# PX4uNode_V0_1_3.net
KiCad netlist of a schematic drawn in EAGLE
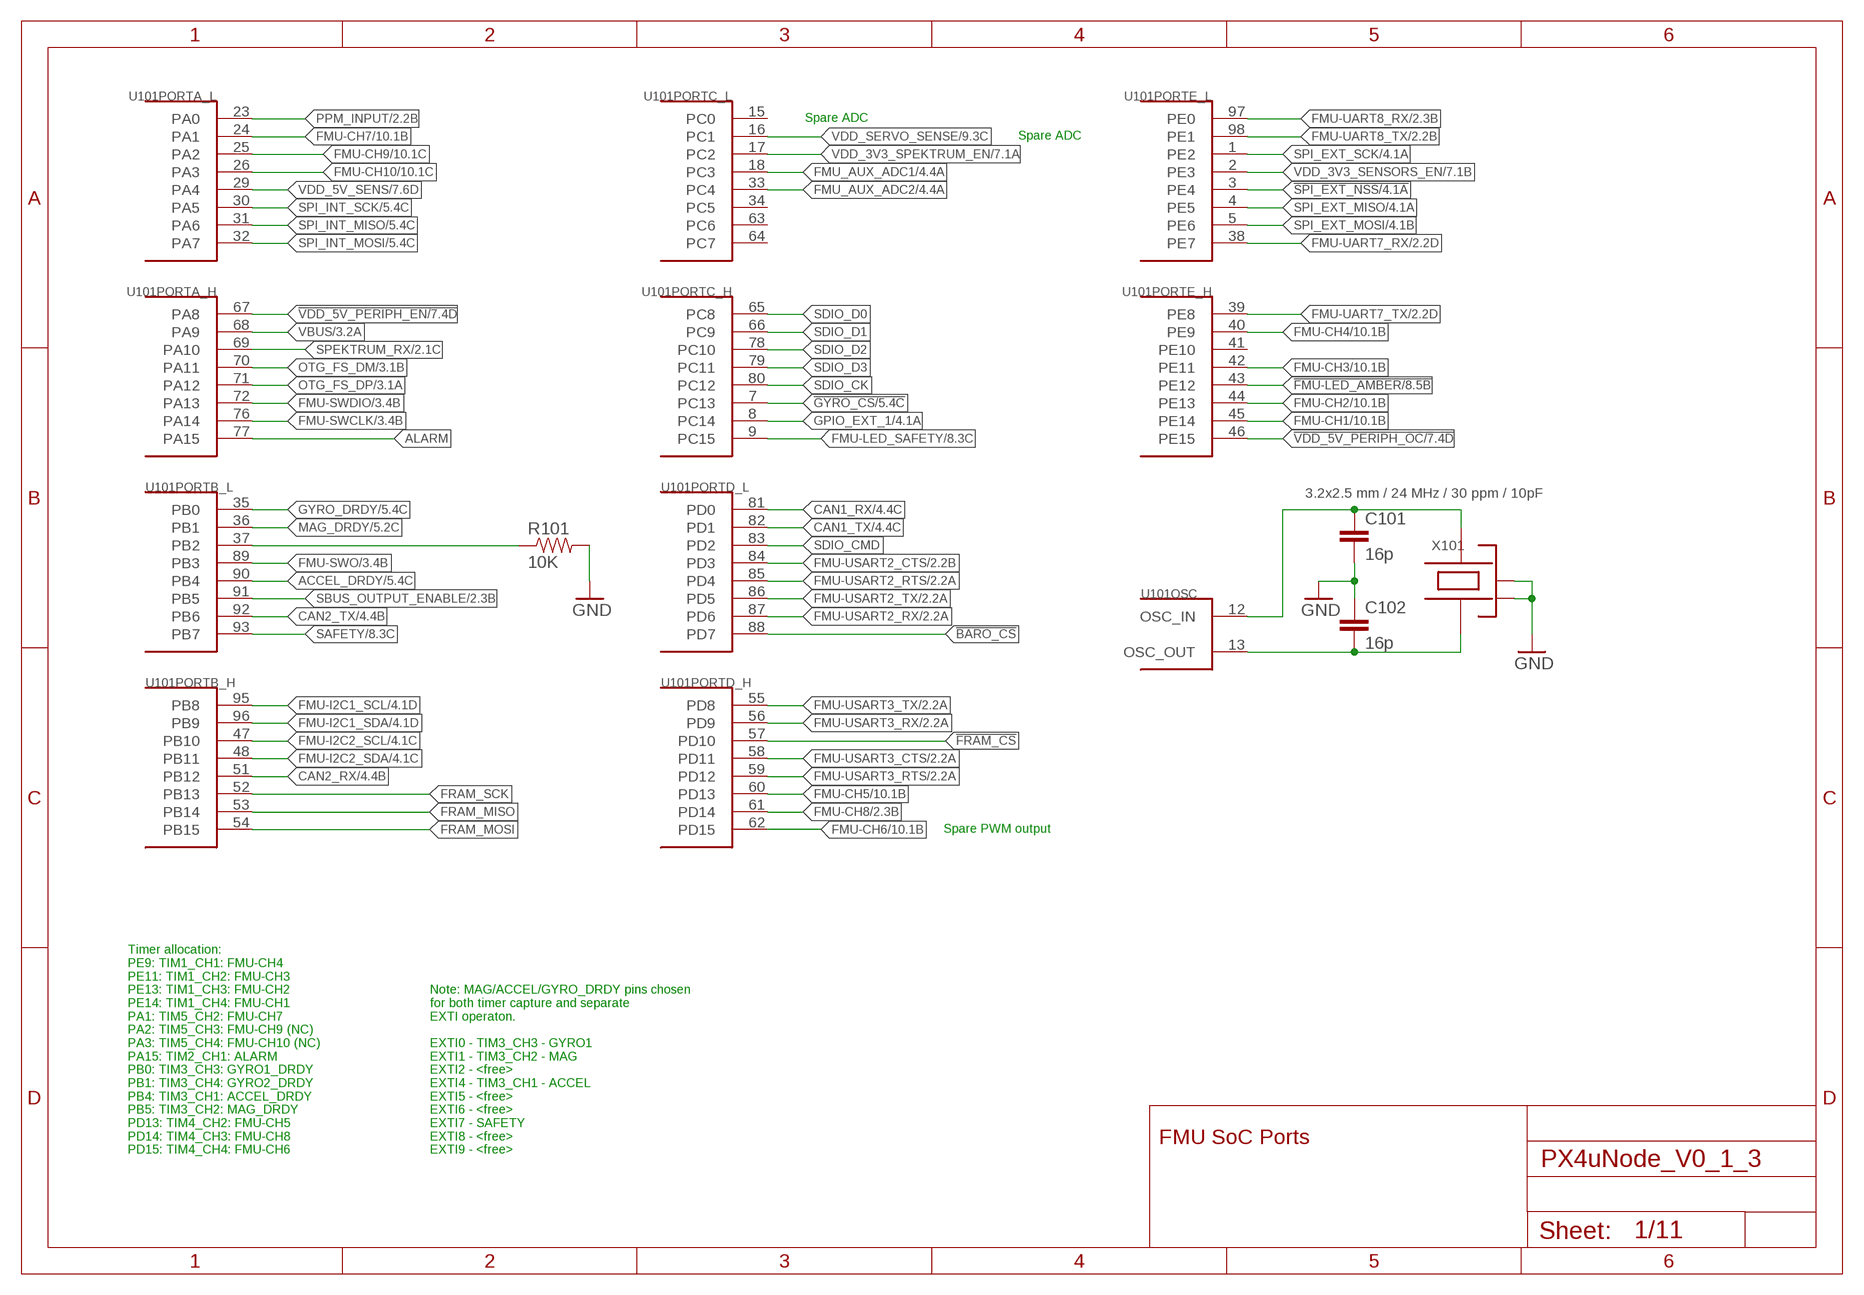
[diagram p0: schematic, sheet 1]
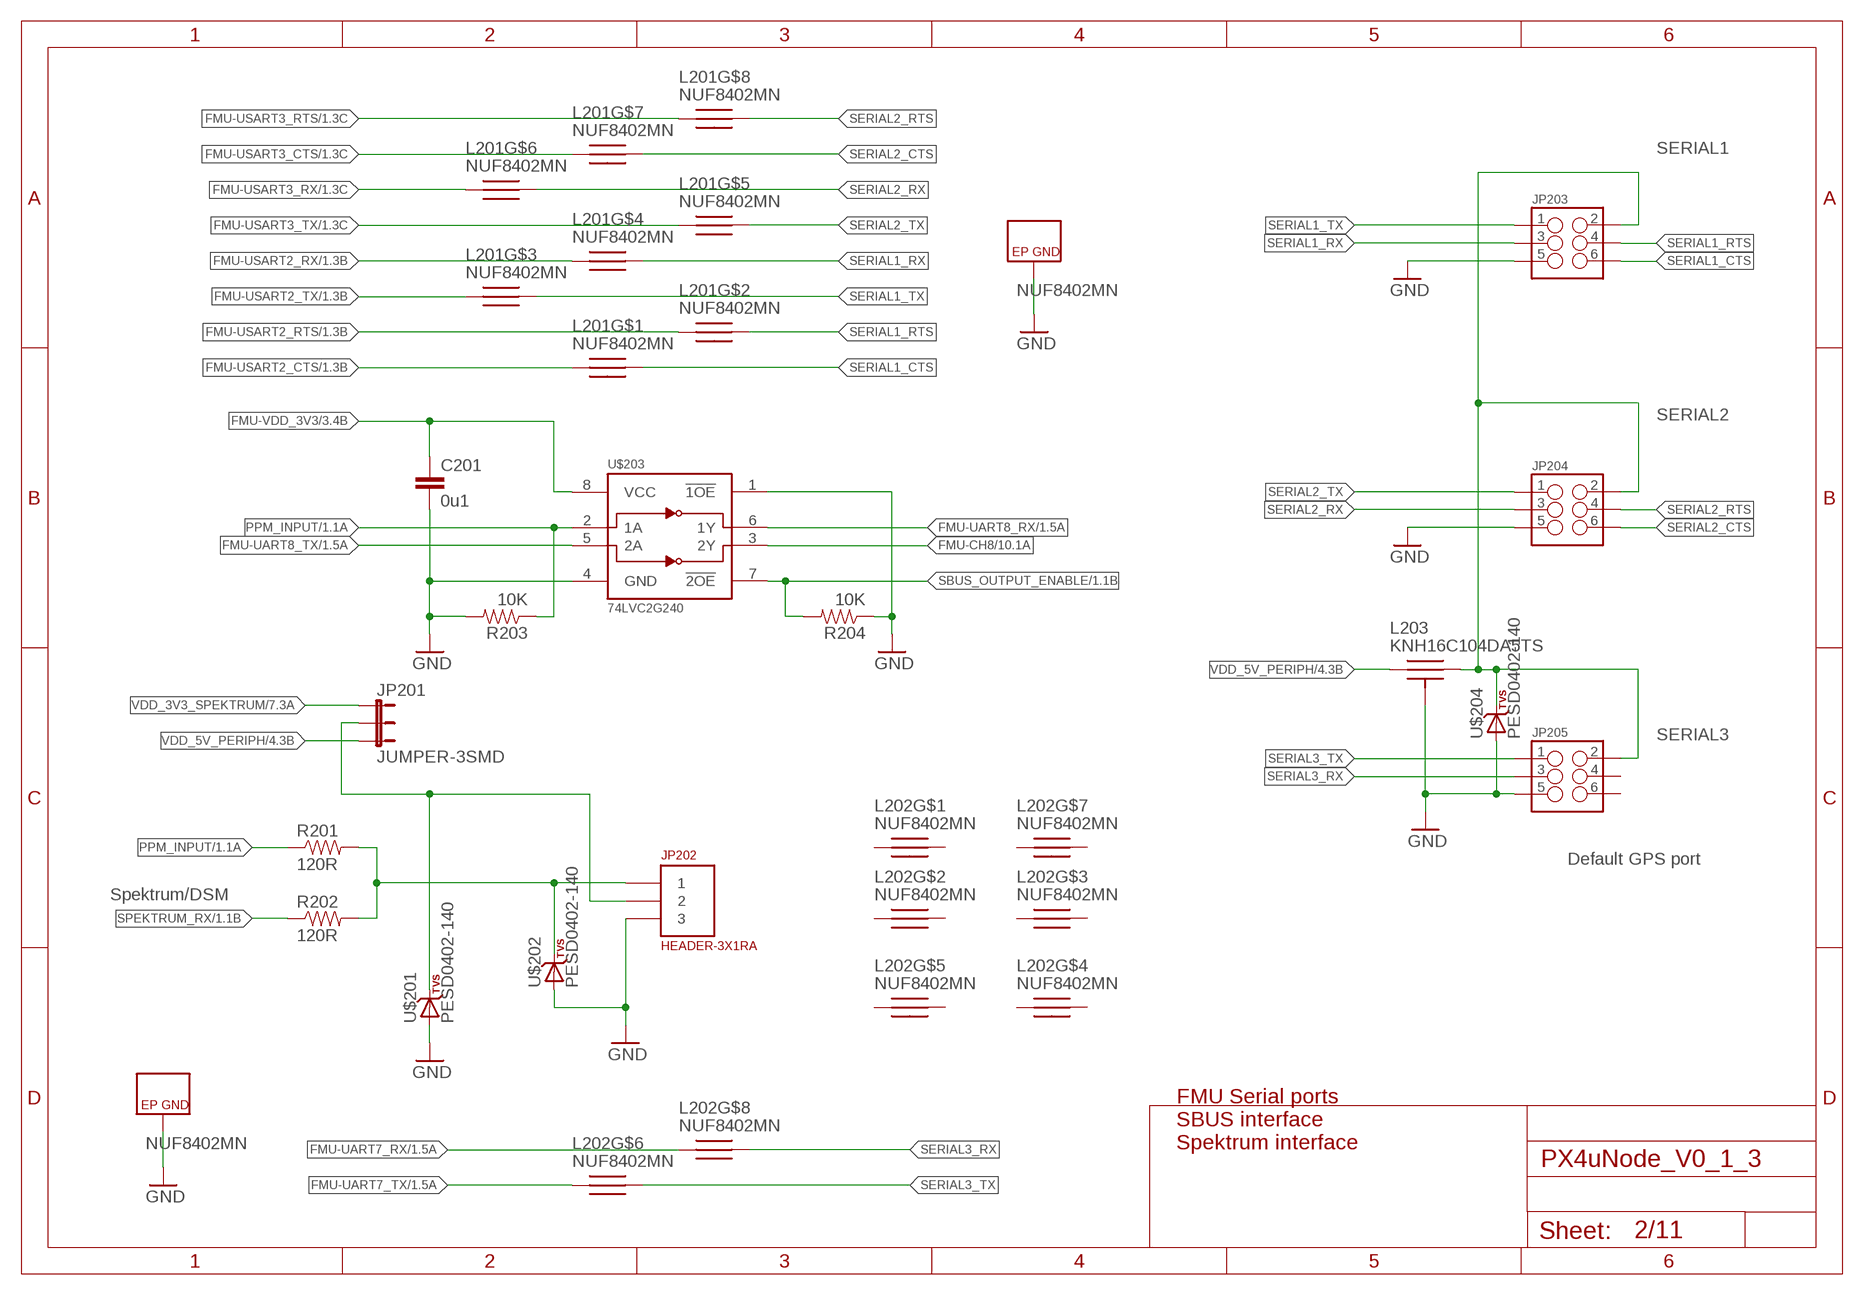
[diagram p1: schematic, sheet 2]
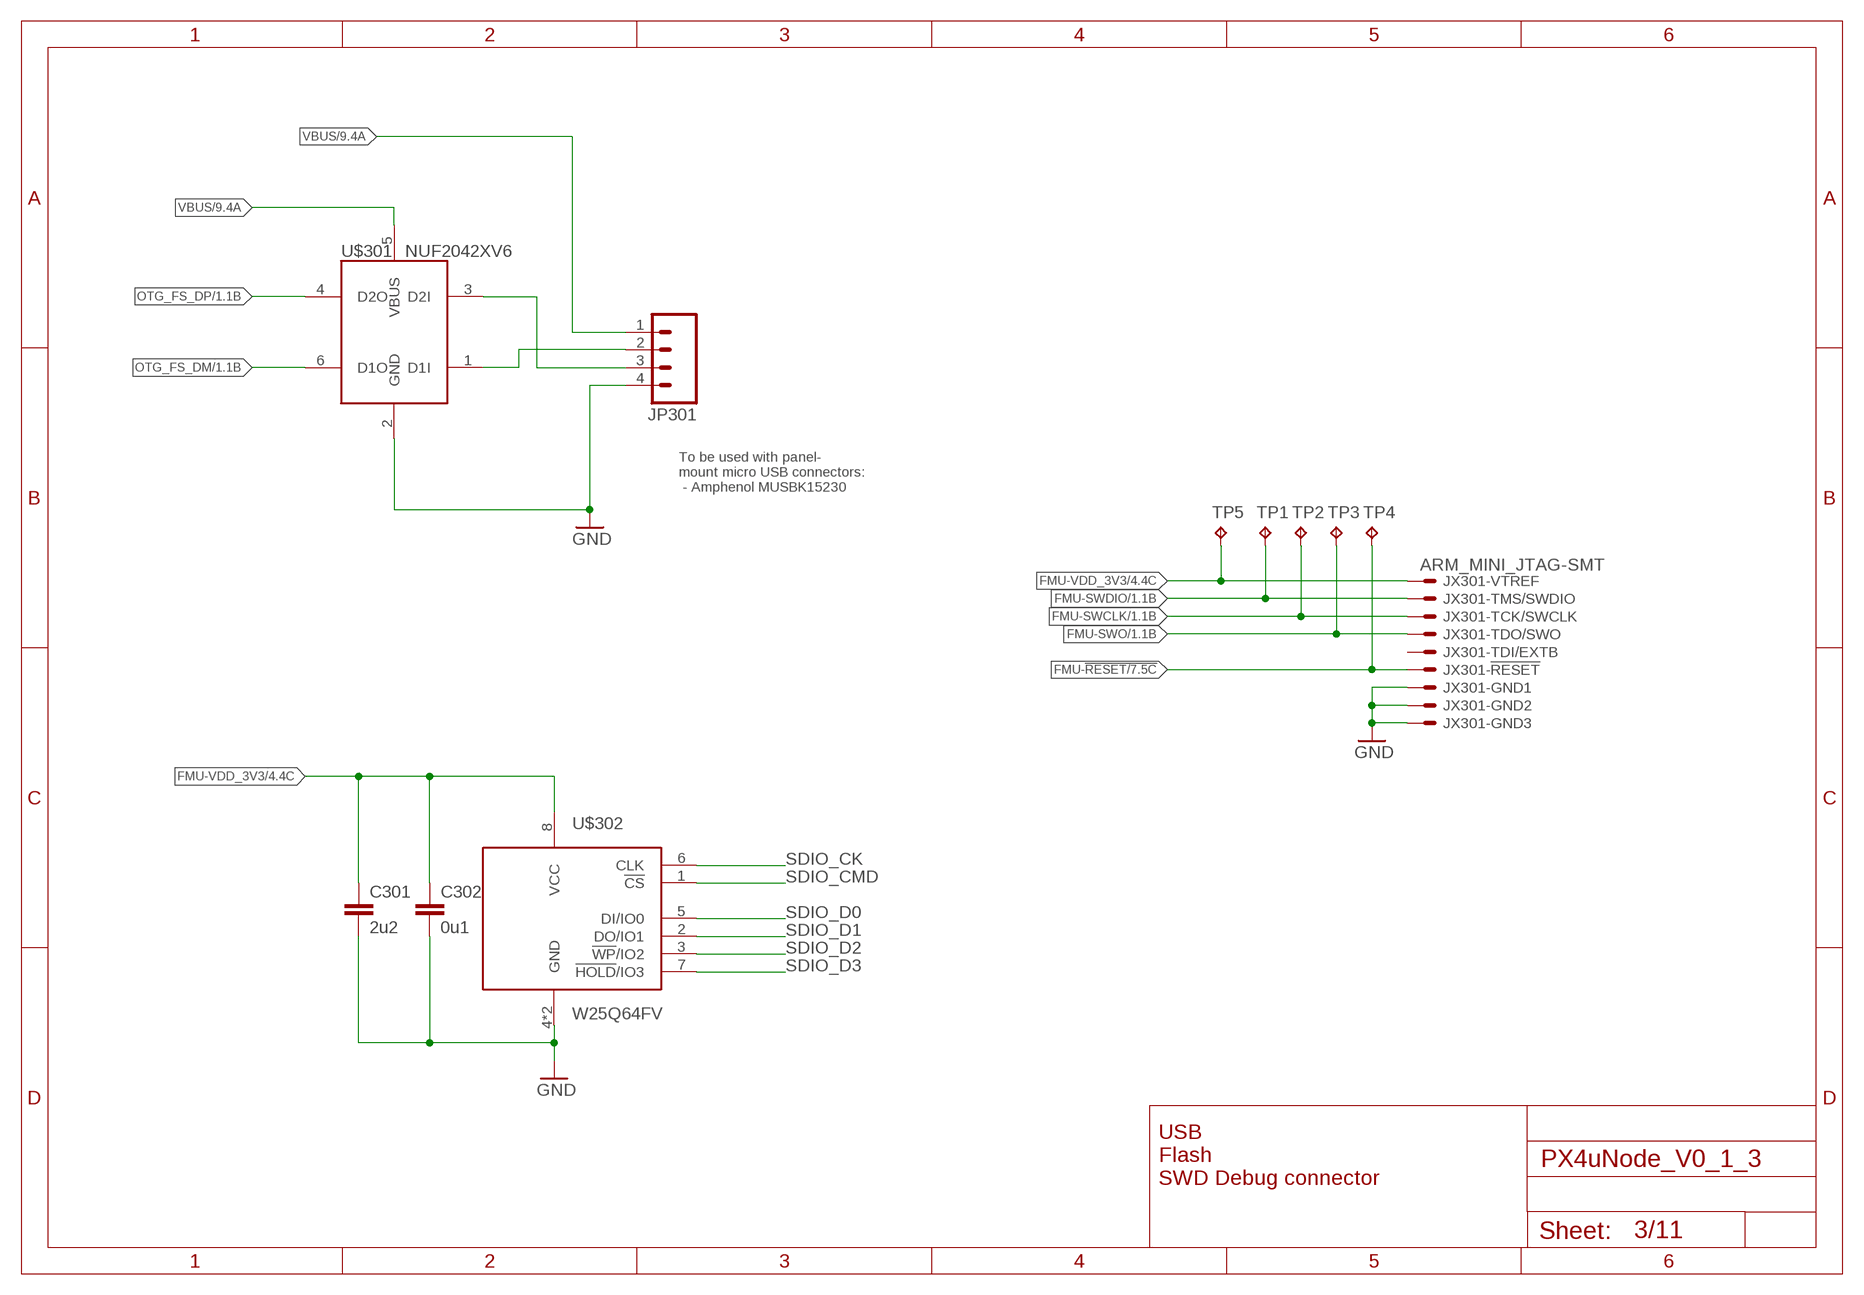
[diagram p2: schematic, sheet 3]
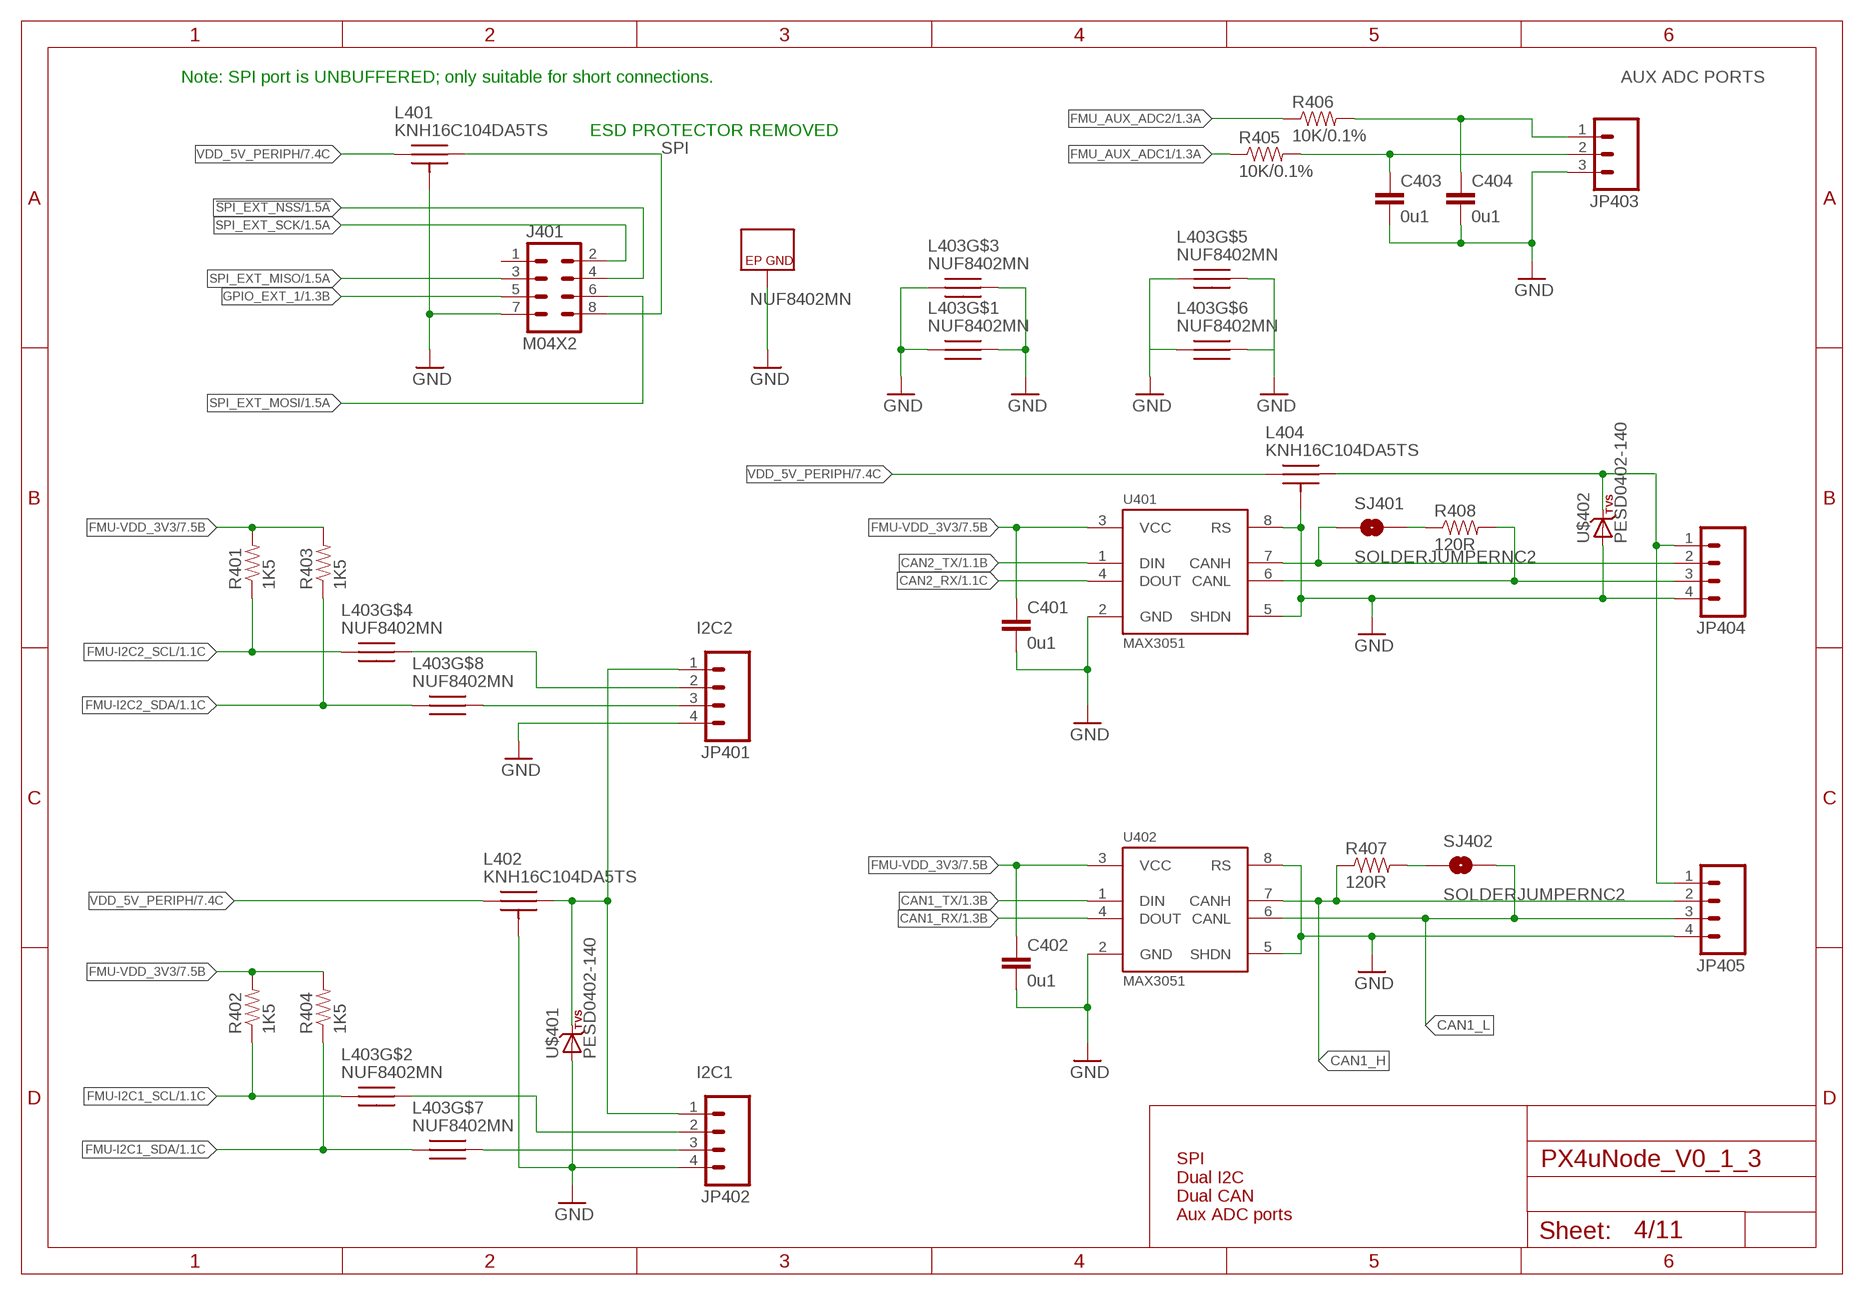
[diagram p3: schematic, sheet 4]
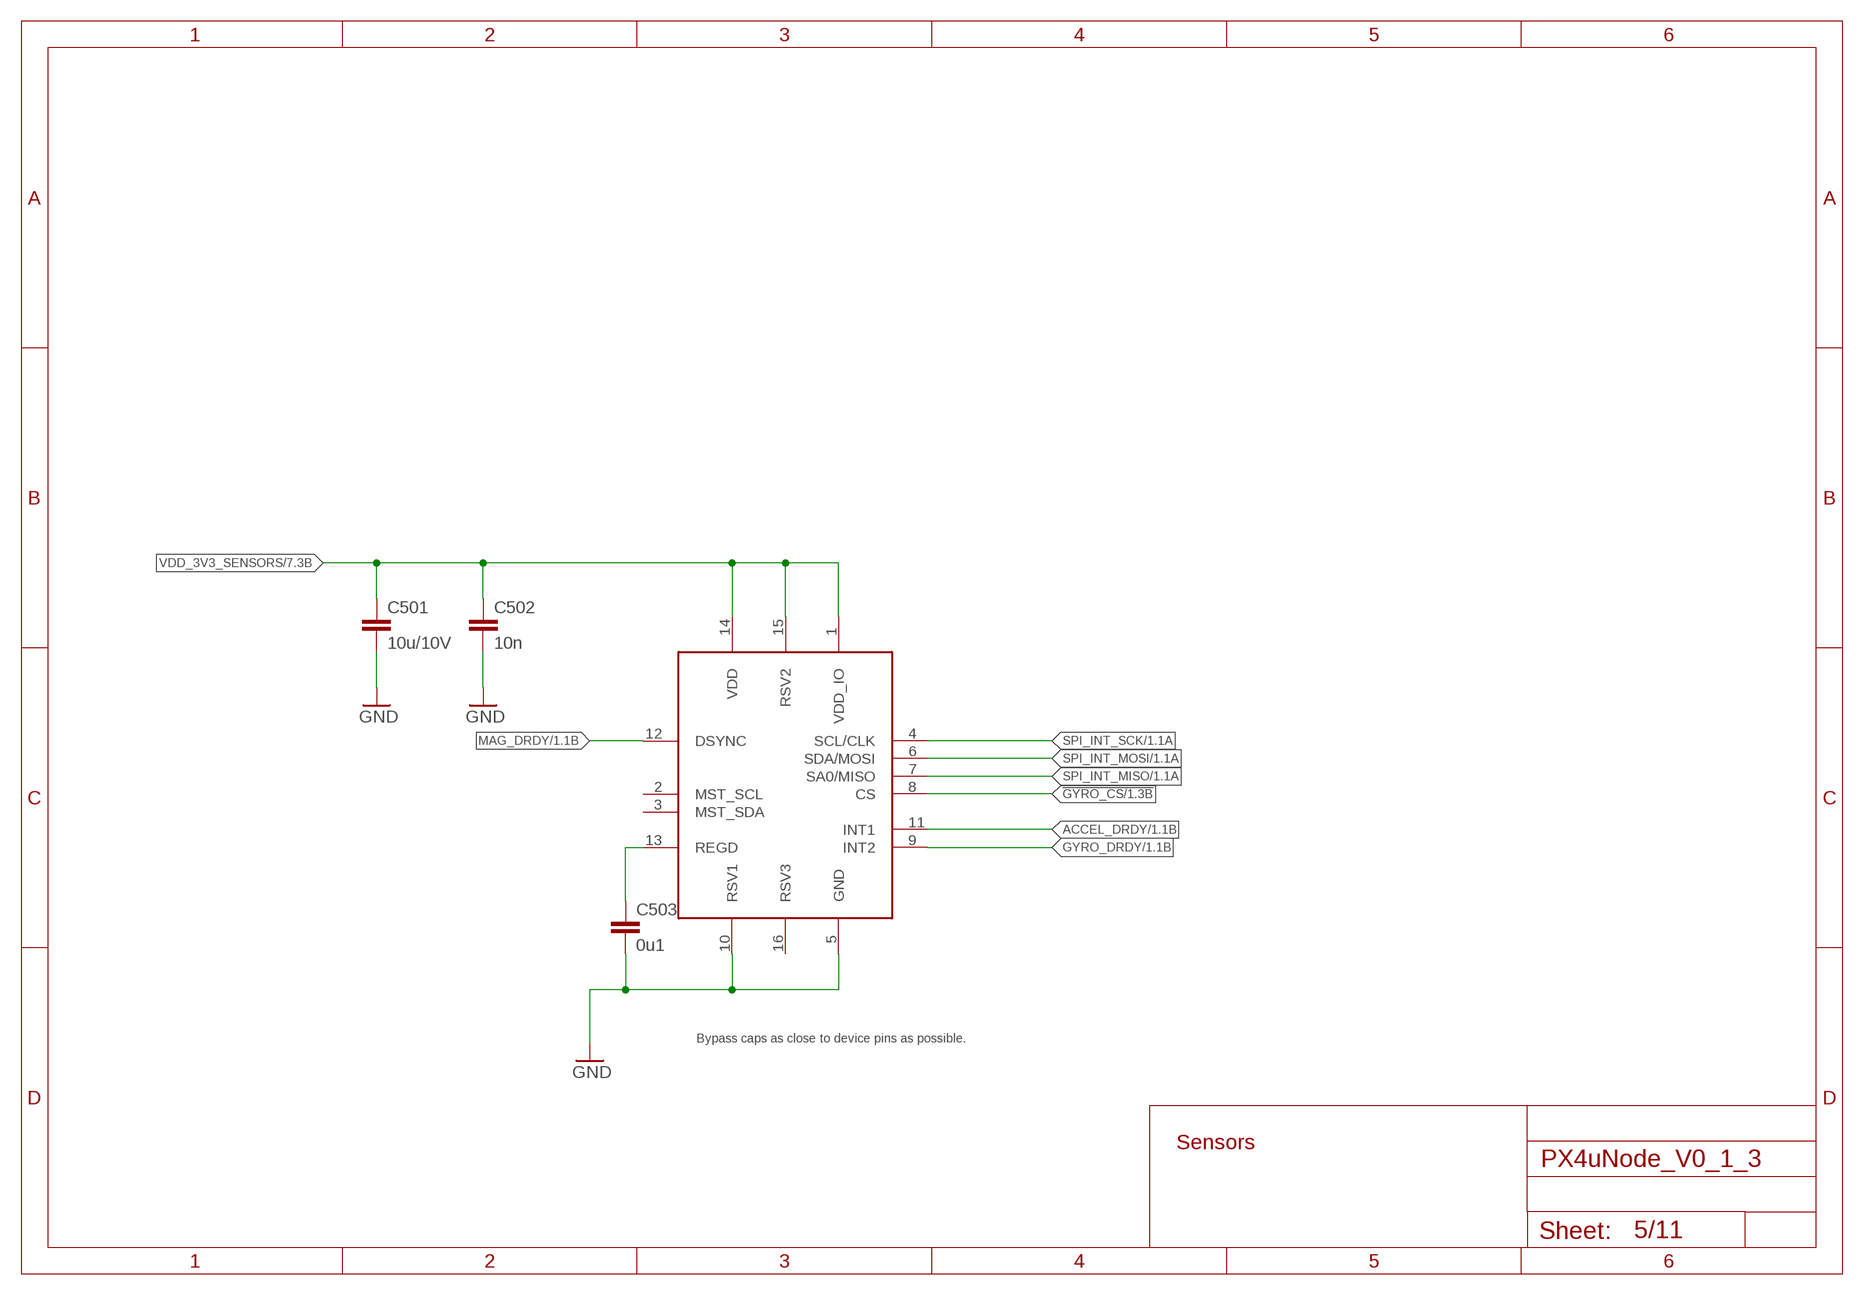
[diagram p4: schematic, sheet 5]
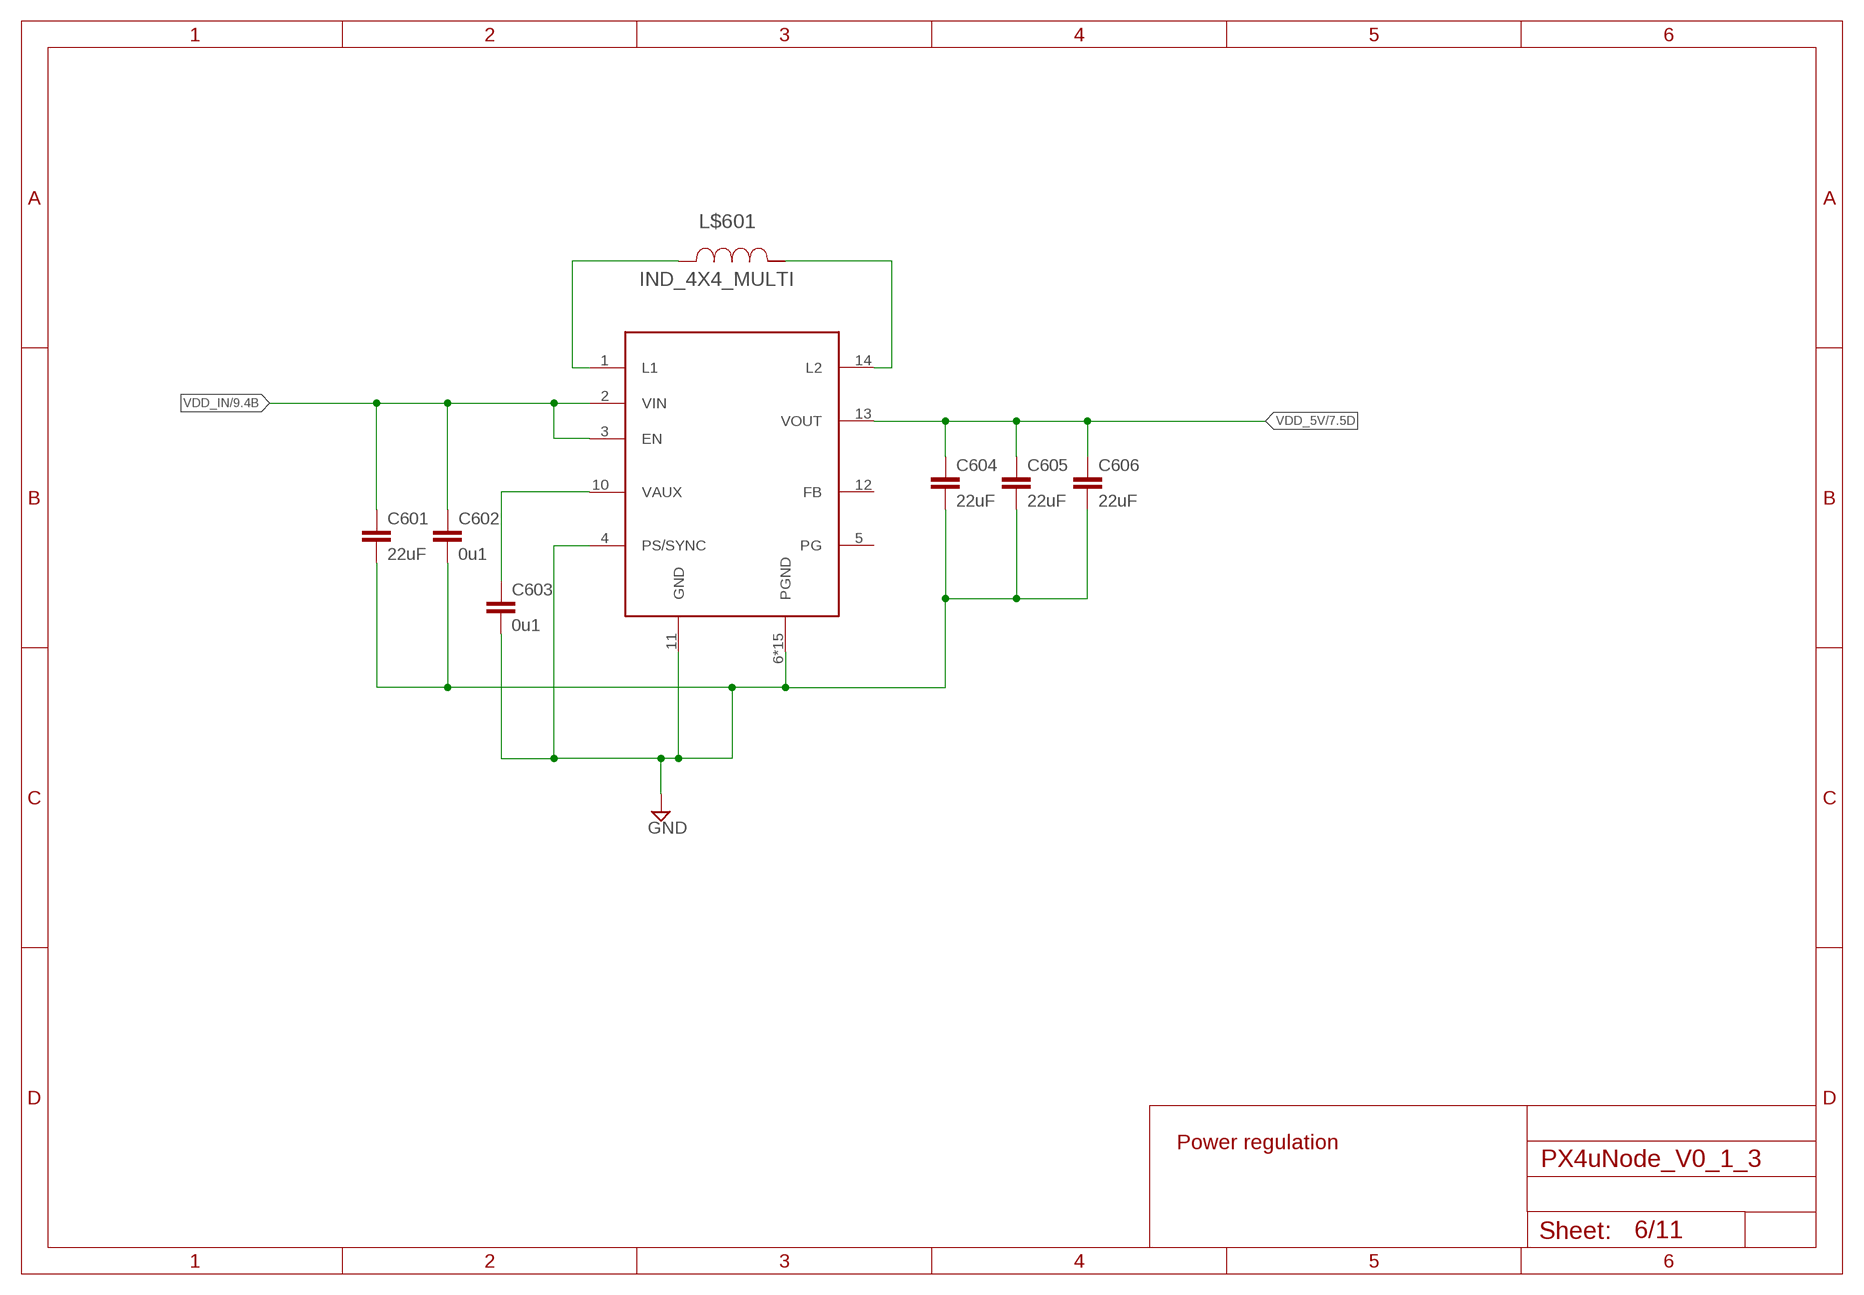
[diagram p5: schematic, sheet 6]
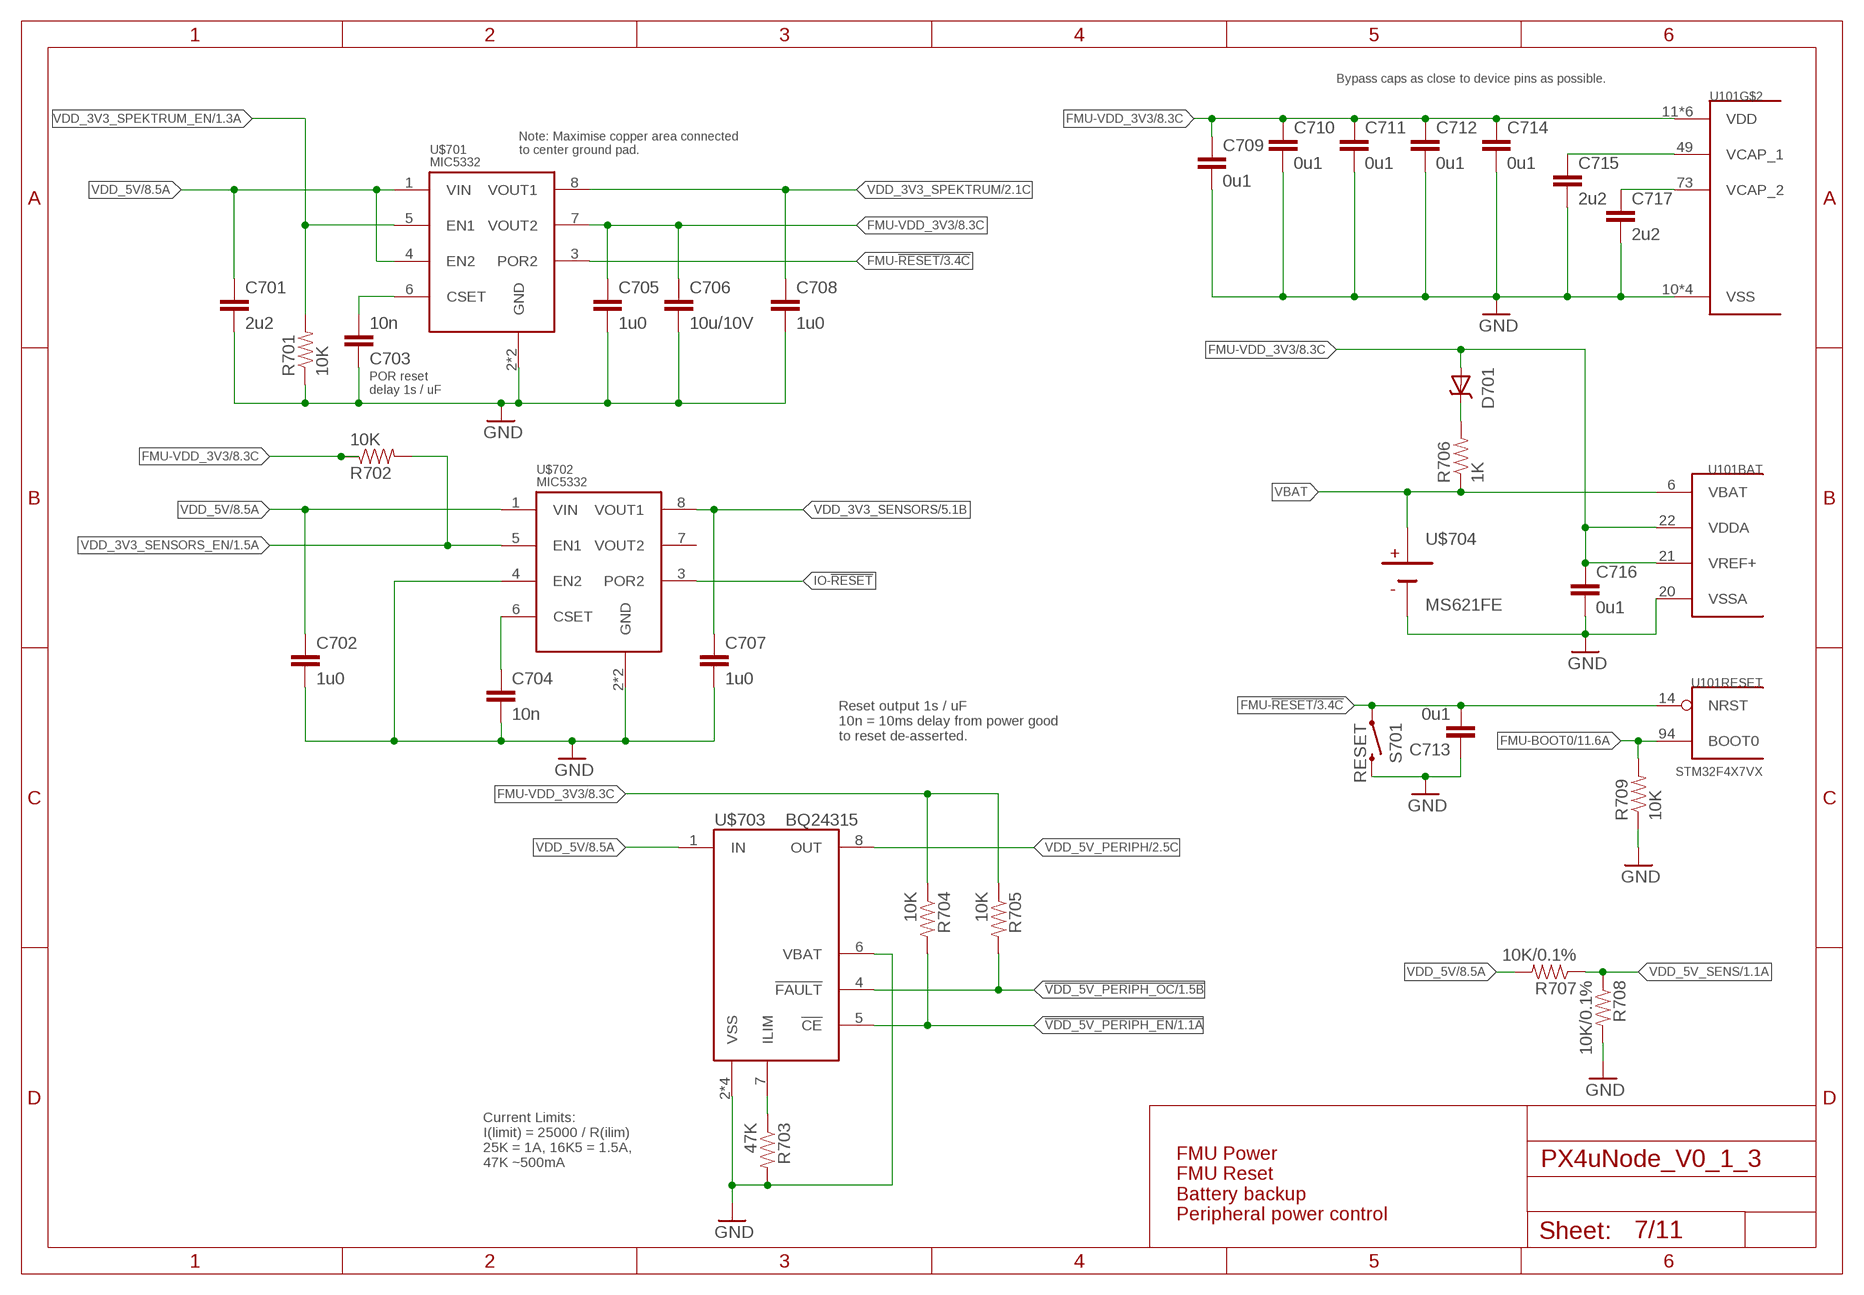
[diagram p6: schematic, sheet 7]
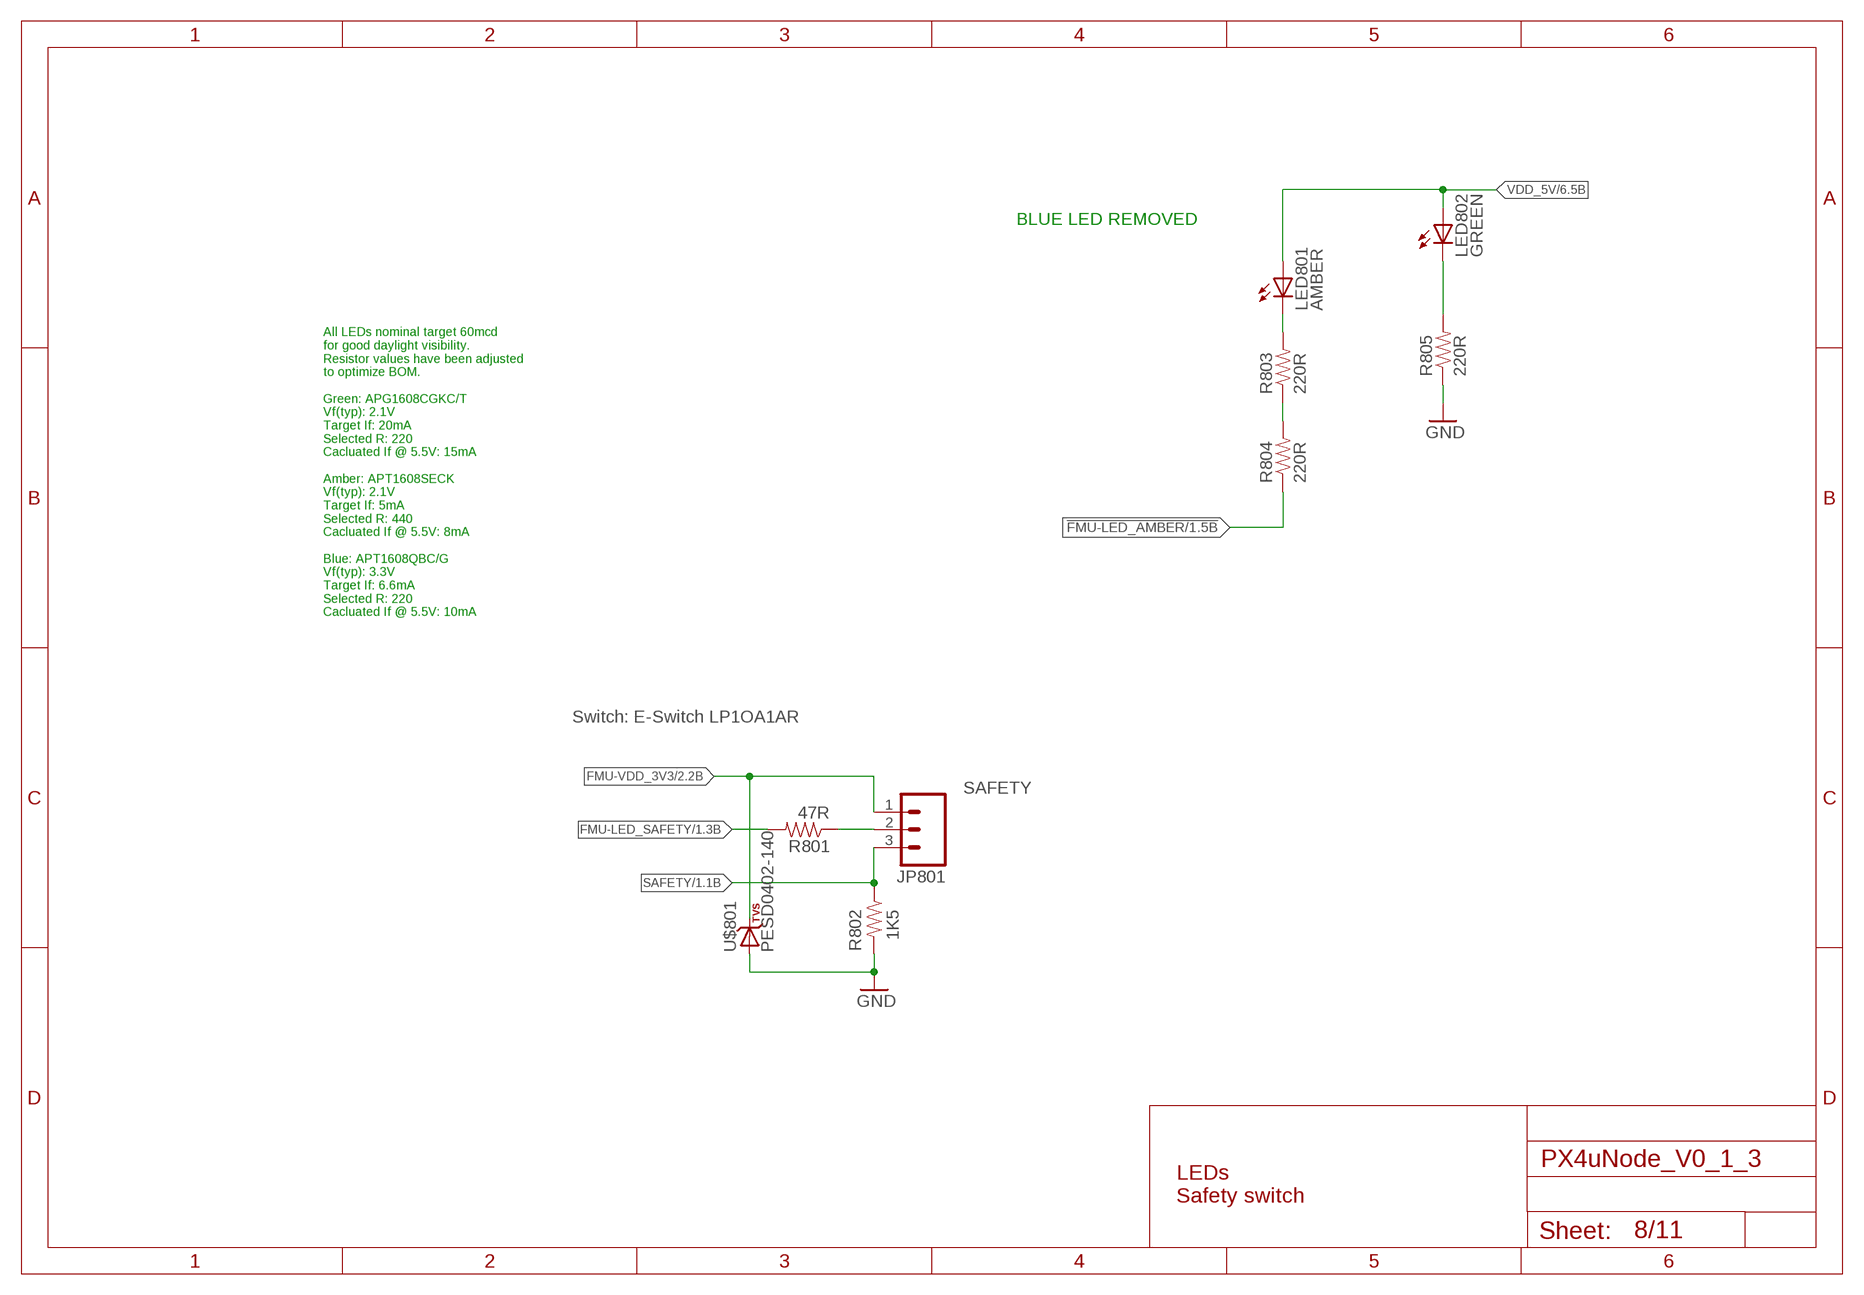
[diagram p7: schematic, sheet 8]
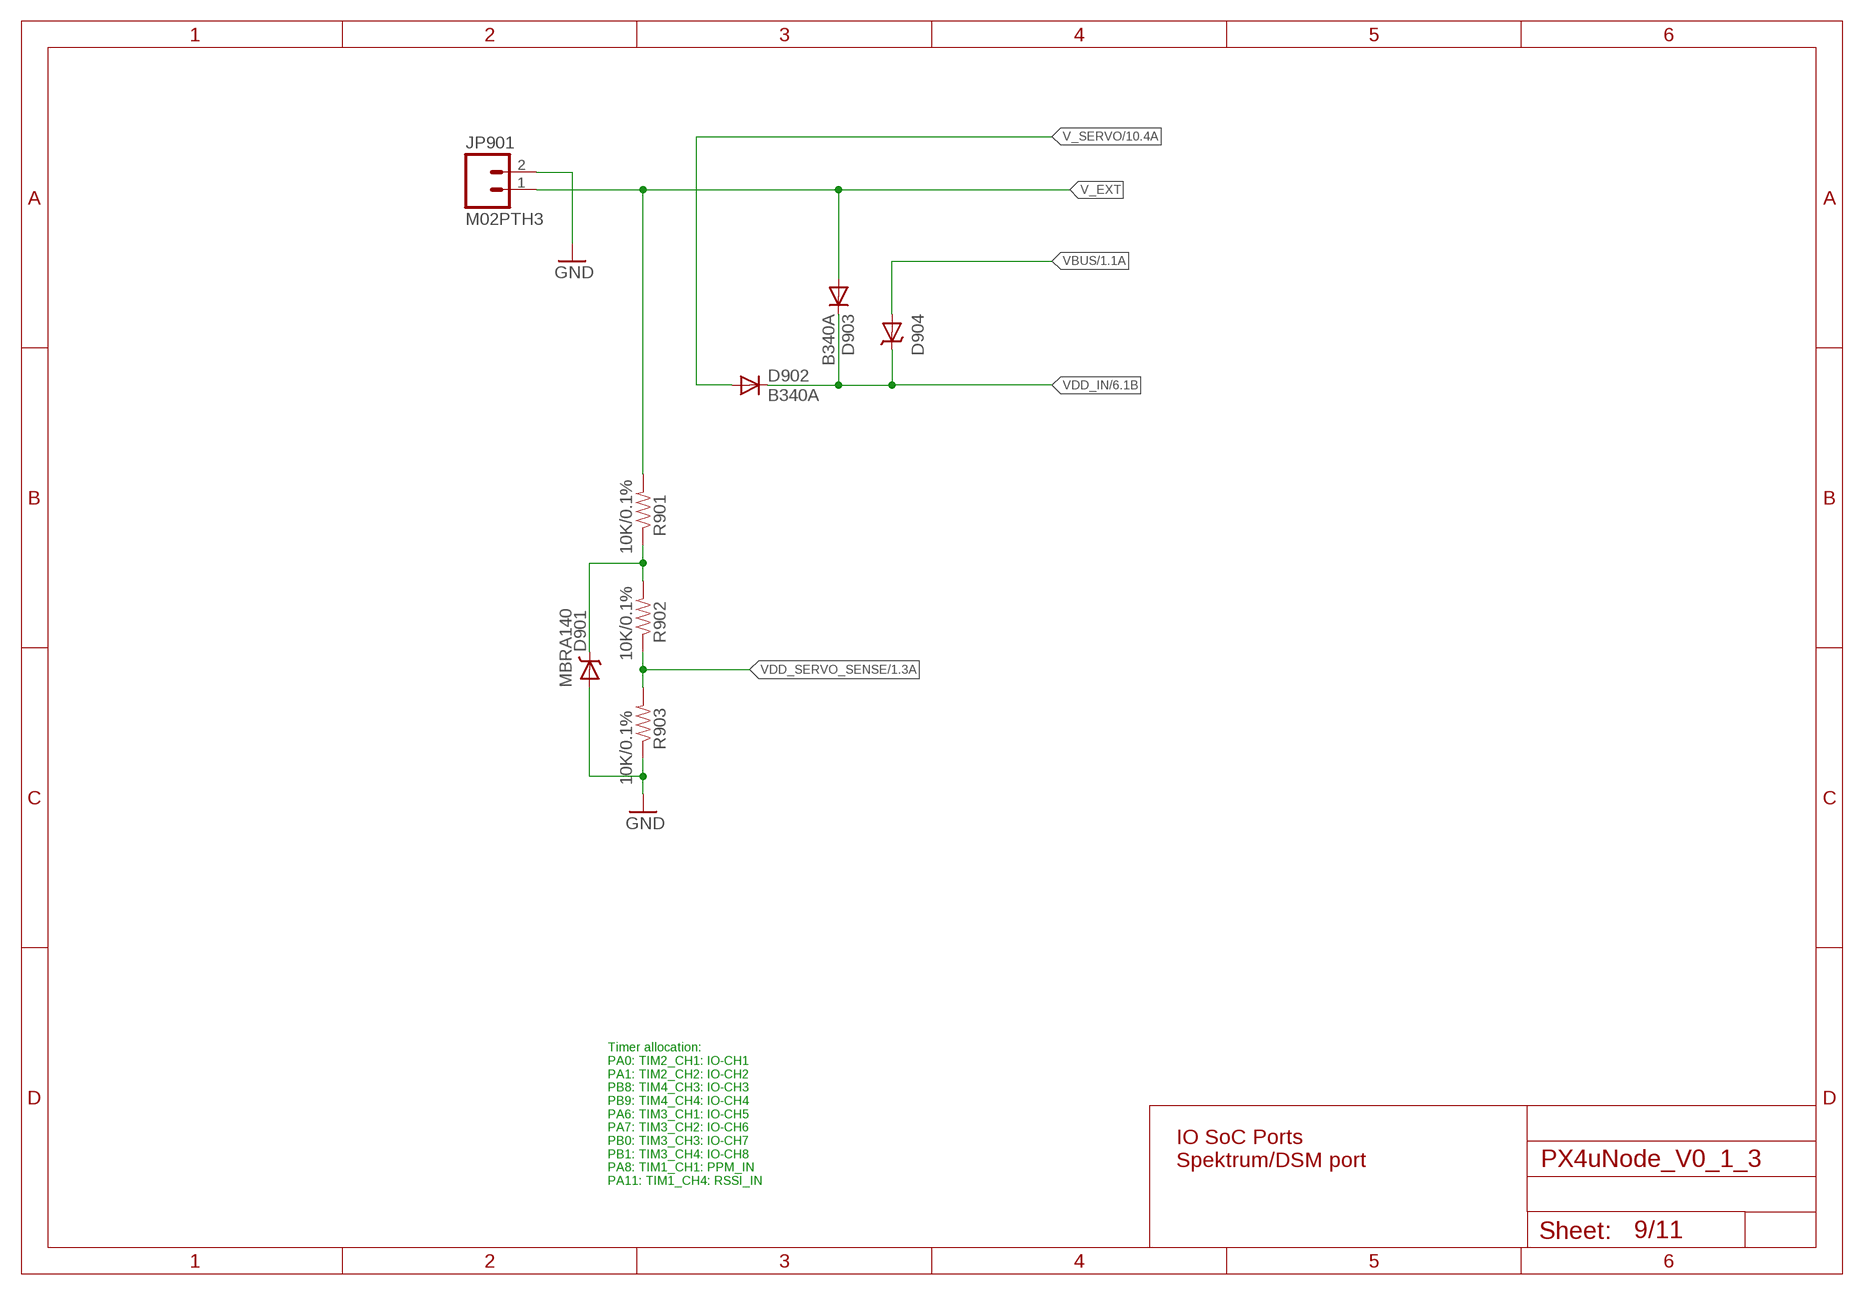
[diagram p8: schematic, sheet 9]
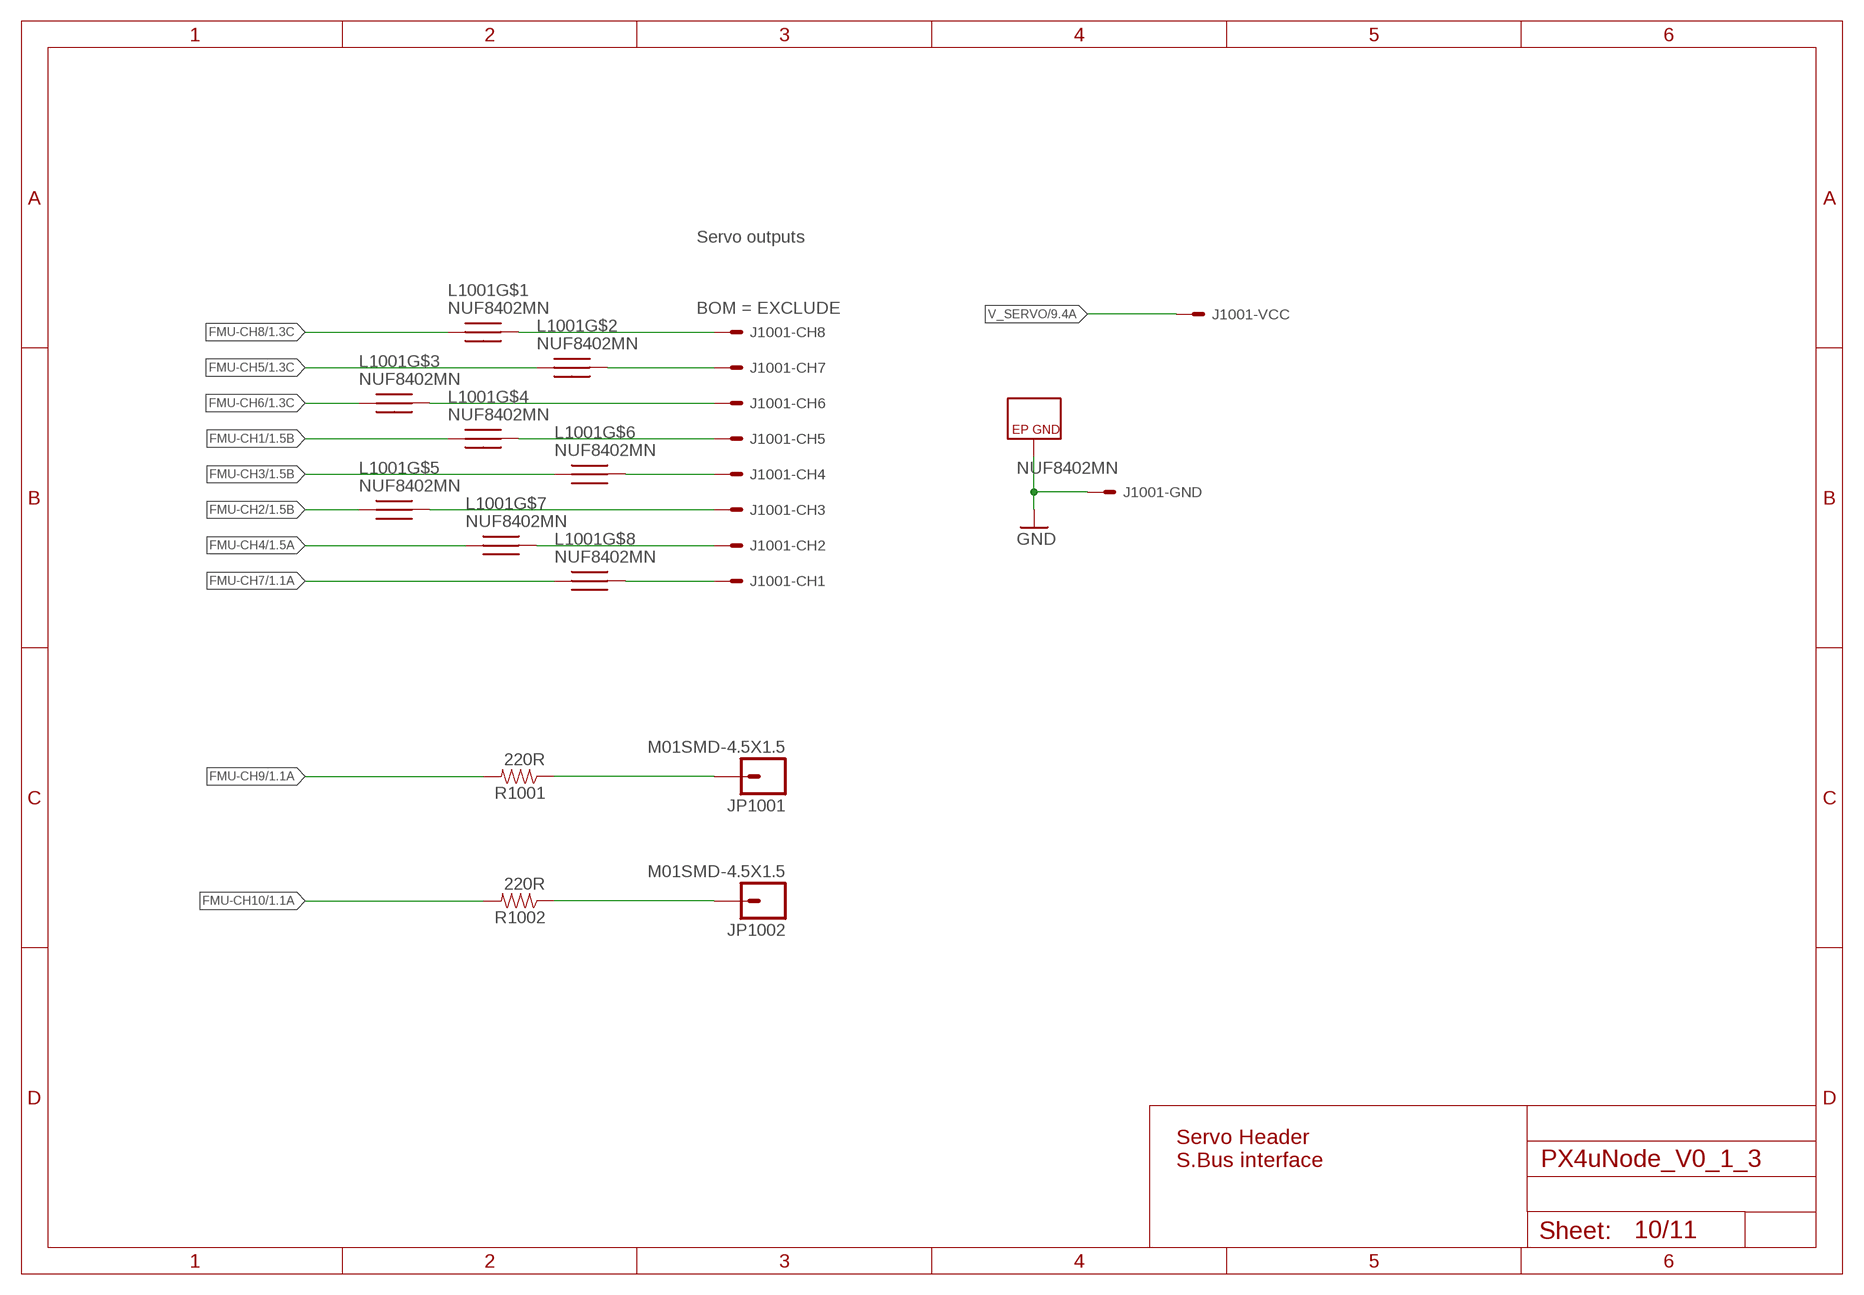
[diagram p9: schematic, sheet 10]
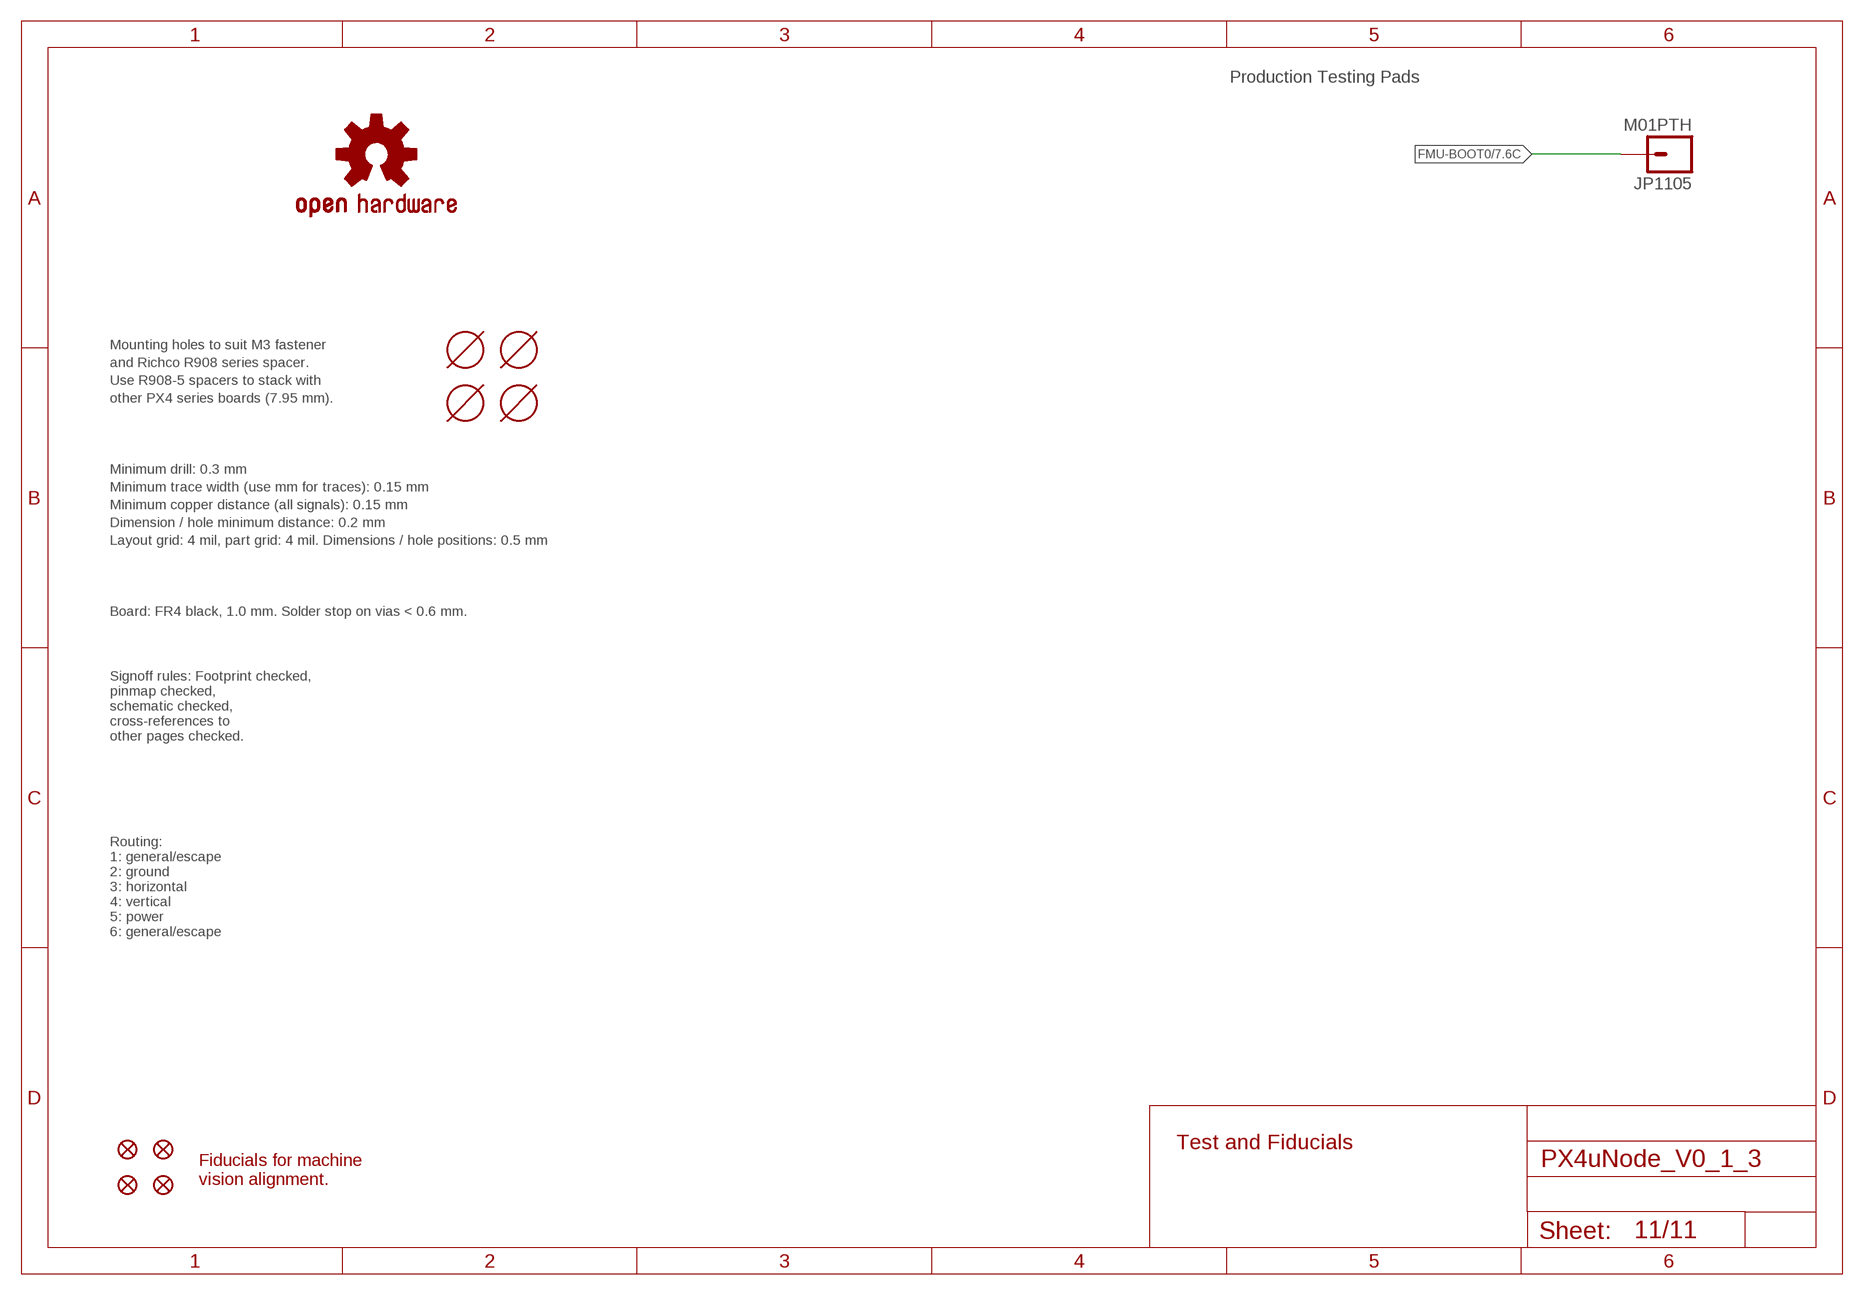
[diagram p10: schematic, sheet 11]

(export (version "E")
  (design (tool "Eeschema 10.0.6"))
  (components
    (comp (ref "C601")
      (value "22uF")
      (footprint "eagle-import:1210")
      (fields (field (name "PARTNO") "C3225X7R1C226M250AC"))
      (libsource (lib "eagle-import") (part "22UF-16V-20%-(1210)"))
    )
    (comp (ref "C602")
      (value "0u1")
      (footprint "eagle-import:0402-CAP")
      (fields (field (name "PARTNO") "CC0402ZRY5V7BB104"))
      (libsource (lib "eagle-import") (part "CAP0402"))
    )
    (comp (ref "C603")
      (value "0u1")
      (footprint "eagle-import:0402-CAP")
      (fields (field (name "PARTNO") "CC0402ZRY5V7BB104"))
      (libsource (lib "eagle-import") (part "CAP0402"))
    )
    (comp (ref "C604")
      (value "22uF")
      (footprint "eagle-import:1210")
      (fields (field (name "PARTNO") "C3225X7R1C226M250AC"))
      (libsource (lib "eagle-import") (part "22UF-16V-20%-(1210)"))
    )
    (comp (ref "C605")
      (value "22uF")
      (footprint "eagle-import:1210")
      (fields (field (name "PARTNO") "C3225X7R1C226M250AC"))
      (libsource (lib "eagle-import") (part "22UF-16V-20%-(1210)"))
    )
    (comp (ref "C606")
      (value "22uF")
      (footprint "eagle-import:1210")
      (fields (field (name "PARTNO") "C3225X7R1C226M250AC"))
      (libsource (lib "eagle-import") (part "22UF-16V-20%-(1210)"))
    )
    (comp (ref "L$601")
      (value "IND_4X4_MULTI")
      (footprint "eagle-import:IND_4X4_MULTI")
      (fields (field (name "MANUFACTURER_PART_NUMBER") "XFL4020-222MEB"))
      (libsource (lib "eagle-import") (part "IND_4X4_MULTI"))
    )
    (comp (ref "U$601")
      (value "TPS6303X")
      (footprint "eagle-import:PWSON10")
      (fields (field (name "PARTNO") "TPS63061DSCT"))
      (libsource (lib "eagle-import") (part "TPS6303X"))
    )
    (comp (ref "C201")
      (value "0u1")
      (footprint "eagle-import:0402-CAP")
      (fields (field (name "PARTNO") "CC0402ZRY5V7BB104"))
      (libsource (lib "eagle-import") (part "CAP0402"))
    )
    (comp (ref "JP201")
      (value "JUMPER-3SMD")
      (footprint "eagle-import:SJ_3")
      (libsource (lib "eagle-import") (part "JUMPER-3SMD"))
    )
    (comp (ref "JP202")
      (value "HEADER-3X1RA")
      (footprint "eagle-import:3X1RA")
      (libsource (lib "eagle-import") (part "HEADER-3X1RA"))
    )
    (comp (ref "JP203")
      (value "M03X22X3_SILK_SM")
      (footprint "eagle-import:2X3")
      (libsource (lib "eagle-import") (part "M03X22X3_SILK_SM"))
    )
    (comp (ref "JP204")
      (value "M03X22X3_SILK_SM")
      (footprint "eagle-import:2X3")
      (libsource (lib "eagle-import") (part "M03X22X3_SILK_SM"))
    )
    (comp (ref "JP205")
      (value "M03X22X3_SILK_SM")
      (footprint "eagle-import:2X3")
      (libsource (lib "eagle-import") (part "M03X22X3_SILK_SM"))
    )
    (comp (ref "L201")
      (value "NUF8402MN")
      (footprint "eagle-import:DFN16-THIN")
      (fields (field (name "PARTNO") "NUF8402MN"))
      (libsource (lib "eagle-import") (part "NUF8402MN"))
    )
    (comp (ref "L202")
      (value "NUF8402MN")
      (footprint "eagle-import:DFN16-THIN")
      (fields (field (name "PARTNO") "NUF8402MN"))
      (libsource (lib "eagle-import") (part "NUF8402MN"))
    )
    (comp (ref "L203")
      (value "KNH16C104DA5TS")
      (footprint "eagle-import:KYOCERA-KNH16-DA")
      (libsource (lib "eagle-import") (part "KNH16C104DA5TS"))
    )
    (comp (ref "R201")
      (value "120R")
      (footprint "eagle-import:0402-RES")
      (fields (field (name "PARTNO") "RC0402FR-07120RL"))
      (libsource (lib "eagle-import") (part "RESISTOR0402-RES"))
    )
    (comp (ref "R202")
      (value "120R")
      (footprint "eagle-import:0402-RES")
      (fields (field (name "PARTNO") "RC0402FR-07120RL"))
      (libsource (lib "eagle-import") (part "RESISTOR0402-RES"))
    )
    (comp (ref "R203")
      (value "10K")
      (footprint "eagle-import:0402-RES")
      (fields (field (name "PARTNO") "RC0402FR-0710KL"))
      (libsource (lib "eagle-import") (part "RESISTOR0402-RES"))
    )
    (comp (ref "R204")
      (value "10K")
      (footprint "eagle-import:0402-RES")
      (fields (field (name "PARTNO") "RC0402FR-0710KL"))
      (libsource (lib "eagle-import") (part "RESISTOR0402-RES"))
    )
    (comp (ref "U$201")
      (value "PESD0402-140")
      (footprint "eagle-import:0402-TVS")
      (libsource (lib "eagle-import") (part "DIODE-TVS"))
    )
    (comp (ref "U$202")
      (value "PESD0402-140")
      (footprint "eagle-import:0402-TVS")
      (libsource (lib "eagle-import") (part "DIODE-TVS"))
    )
    (comp (ref "U$203")
      (value "74LVC2G240")
      (footprint "eagle-import:VSSOP8")
      (libsource (lib "eagle-import") (part "74LVC2G240"))
    )
    (comp (ref "U$204")
      (value "PESD0402-140")
      (footprint "eagle-import:0402-TVS")
      (libsource (lib "eagle-import") (part "DIODE-TVS"))
    )
    (comp (ref "C701")
      (value "2u2")
      (footprint "eagle-import:0603-CAP")
      (fields (field (name "PARTNO") "C1608Y5V1C225Z"))
      (libsource (lib "eagle-import") (part "CAP0603"))
    )
    (comp (ref "C702")
      (value "1u0")
      (footprint "eagle-import:0603-CAP")
      (fields (field (name "PARTNO") "CC0603ZRY5V7BB105"))
      (libsource (lib "eagle-import") (part "CAP0603"))
    )
    (comp (ref "C703")
      (value "10n")
      (footprint "eagle-import:0402-CAP")
      (fields (field (name "PARTNO") "CC0402KRX7R7BB103"))
      (libsource (lib "eagle-import") (part "CAP0402"))
    )
    (comp (ref "C704")
      (value "10n")
      (footprint "eagle-import:0402-CAP")
      (fields (field (name "PARTNO") "CC0402KRX7R7BB103"))
      (libsource (lib "eagle-import") (part "CAP0402"))
    )
    (comp (ref "C705")
      (value "1u0")
      (footprint "eagle-import:0603-CAP")
      (fields (field (name "PARTNO") "CC0603ZRY5V7BB105"))
      (libsource (lib "eagle-import") (part "CAP0603"))
    )
    (comp (ref "C706")
      (value "10u/10V")
      (footprint "eagle-import:0805-CAP")
      (fields (field (name "PARTNO") "CC0805ZKY5V6BB106"))
      (libsource (lib "eagle-import") (part "CAP0805"))
    )
    (comp (ref "C707")
      (value "1u0")
      (footprint "eagle-import:0603-CAP")
      (fields (field (name "PARTNO") "CC0603ZRY5V7BB105"))
      (libsource (lib "eagle-import") (part "CAP0603"))
    )
    (comp (ref "C708")
      (value "1u0")
      (footprint "eagle-import:0603-CAP")
      (fields (field (name "PARTNO") "CC0603ZRY5V7BB105"))
      (libsource (lib "eagle-import") (part "CAP0603"))
    )
    (comp (ref "C709")
      (value "0u1")
      (footprint "eagle-import:0402-CAP")
      (fields (field (name "PARTNO") "CC0402ZRY5V7BB104"))
      (libsource (lib "eagle-import") (part "CAP0402"))
    )
    (comp (ref "C710")
      (value "0u1")
      (footprint "eagle-import:0402-CAP")
      (fields (field (name "PARTNO") "CC0402ZRY5V7BB104"))
      (libsource (lib "eagle-import") (part "CAP0402"))
    )
    (comp (ref "C711")
      (value "0u1")
      (footprint "eagle-import:0402-CAP")
      (fields (field (name "PARTNO") "CC0402ZRY5V7BB104"))
      (libsource (lib "eagle-import") (part "CAP0402"))
    )
    (comp (ref "C712")
      (value "0u1")
      (footprint "eagle-import:0402-CAP")
      (fields (field (name "PARTNO") "CC0402ZRY5V7BB104"))
      (libsource (lib "eagle-import") (part "CAP0402"))
    )
    (comp (ref "C713")
      (value "0u1")
      (footprint "eagle-import:0402-CAP")
      (fields (field (name "PARTNO") "CC0402ZRY5V7BB104"))
      (libsource (lib "eagle-import") (part "CAP0402"))
    )
    (comp (ref "C714")
      (value "0u1")
      (footprint "eagle-import:0402-CAP")
      (fields (field (name "PARTNO") "CC0402ZRY5V7BB104"))
      (libsource (lib "eagle-import") (part "CAP0402"))
    )
    (comp (ref "C715")
      (value "2u2")
      (footprint "eagle-import:0603-CAP")
      (fields (field (name "PARTNO") "C1608Y5V1C225Z"))
      (libsource (lib "eagle-import") (part "CAP0603"))
    )
    (comp (ref "C716")
      (value "0u1")
      (footprint "eagle-import:0402-CAP")
      (fields (field (name "PARTNO") "CC0402ZRY5V7BB104"))
      (libsource (lib "eagle-import") (part "CAP0402"))
    )
    (comp (ref "C717")
      (value "2u2")
      (footprint "eagle-import:0603-CAP")
      (fields (field (name "PARTNO") "C1608Y5V1C225Z"))
      (libsource (lib "eagle-import") (part "CAP0603"))
    )
    (comp (ref "D701")
      (value "DIODE-SCHOTTKY")
      (footprint "eagle-import:SOD-523")
      (fields (field (name "PARTNO") "MBRA140"))
      (libsource (lib "eagle-import") (part "DIODE-SCHOTTKY"))
    )
    (comp (ref "R701")
      (value "10K")
      (footprint "eagle-import:0402-RES")
      (fields (field (name "PARTNO") "RC0402FR-0710KL"))
      (libsource (lib "eagle-import") (part "RESISTOR0402-RES"))
    )
    (comp (ref "R702")
      (value "10K")
      (footprint "eagle-import:0402-RES")
      (fields (field (name "PARTNO") "RC0402FR-0710KL"))
      (libsource (lib "eagle-import") (part "RESISTOR0402-RES"))
    )
    (comp (ref "R703")
      (value "47K")
      (footprint "eagle-import:0402-RES")
      (fields (field (name "PARTNO") "RMCF0402FT47K"))
      (libsource (lib "eagle-import") (part "RESISTOR0402-RES"))
    )
    (comp (ref "R704")
      (value "10K")
      (footprint "eagle-import:0402-RES")
      (fields (field (name "PARTNO") "RC0402FR-0710KL"))
      (libsource (lib "eagle-import") (part "RESISTOR0402-RES"))
    )
    (comp (ref "R705")
      (value "10K")
      (footprint "eagle-import:0402-RES")
      (fields (field (name "PARTNO") "RC0402FR-0710KL"))
      (libsource (lib "eagle-import") (part "RESISTOR0402-RES"))
    )
    (comp (ref "R706")
      (value "1K")
      (footprint "eagle-import:0402-RES")
      (fields (field (name "PARTNO") "RC0402FR-071KL"))
      (libsource (lib "eagle-import") (part "RESISTOR0402-RES"))
    )
    (comp (ref "R707")
      (value "10K/0.1%")
      (footprint "eagle-import:0402-RES")
      (fields (field (name "PARTNO") "ERA-2AEB103X"))
      (libsource (lib "eagle-import") (part "RESISTOR0402-RES"))
    )
    (comp (ref "R708")
      (value "10K/0.1%")
      (footprint "eagle-import:0402-RES")
      (fields (field (name "PARTNO") "ERA-2AEB103X"))
      (libsource (lib "eagle-import") (part "RESISTOR0402-RES"))
    )
    (comp (ref "R709")
      (value "10K")
      (footprint "eagle-import:0402-RES")
      (fields (field (name "PARTNO") "RC0402FR-0710KL"))
      (libsource (lib "eagle-import") (part "RESISTOR0402-RES"))
    )
    (comp (ref "S701")
      (value "RESET")
      (footprint "eagle-import:EVQP7J01K")
      (fields (field (name "PARTNO") "EVQP7J01K"))
      (libsource (lib "eagle-import") (part "SWITCH-MOMENTARY-2"))
    )
    (comp (ref "U$701")
      (value "MIC5332")
      (footprint "eagle-import:MLF-8-EPAD")
      (fields (field (name "PARTNO") "MIC5332-SSYMT"))
      (libsource (lib "eagle-import") (part "MIC5332"))
    )
    (comp (ref "U$702")
      (value "MIC5332")
      (footprint "eagle-import:MLF-8-EPAD")
      (fields (field (name "PARTNO") "MIC5332-SSYMT"))
      (libsource (lib "eagle-import") (part "MIC5332"))
    )
    (comp (ref "U$703")
      (value "BQ24315")
      (footprint "eagle-import:QFN8-DSG")
      (fields (field (name "PARTNO") "BQ24315DSGR"))
      (libsource (lib "eagle-import") (part "BQ24315"))
    )
    (comp (ref "U$704")
      (value "MS621FE")
      (footprint "eagle-import:MS621FE")
      (libsource (lib "eagle-import") (part "MS621FE"))
    )
    (comp (ref "U101")
      (value "STM32F4X7VX")
      (footprint "eagle-import:TQFP100")
      (fields (field (name "PARTNO") "STM32F427VI"))
      (libsource (lib "eagle-import") (part "STM32F4X7VX"))
    )
    (comp (ref "J1001")
      (value "SERVO_HEADER-3X8")
      (footprint "eagle-import:3X8RA_SERVO")
      (fields (field (name "BOM") "EXCLUDE"))
      (libsource (lib "eagle-import") (part "SERVO_HEADER-3X8"))
    )
    (comp (ref "JP1001")
      (value "M01SMD-4.5X1.5")
      (footprint "eagle-import:PAD-1.5X4.5")
      (libsource (lib "eagle-import") (part "M01SMD-4.5X1.5"))
    )
    (comp (ref "JP1002")
      (value "M01SMD-4.5X1.5")
      (footprint "eagle-import:PAD-1.5X4.5")
      (libsource (lib "eagle-import") (part "M01SMD-4.5X1.5"))
    )
    (comp (ref "L1001")
      (value "NUF8402MN")
      (footprint "eagle-import:DFN16-THIN")
      (fields (field (name "PARTNO") "NUF8402MN"))
      (libsource (lib "eagle-import") (part "NUF8402MN"))
    )
    (comp (ref "R1001")
      (value "220R")
      (footprint "eagle-import:0402-RES")
      (fields (field (name "PARTNO") "RC0402FR-07220RL"))
      (libsource (lib "eagle-import") (part "RESISTOR0402-RES"))
    )
    (comp (ref "R1002")
      (value "220R")
      (footprint "eagle-import:0402-RES")
      (fields (field (name "PARTNO") "RC0402FR-07220RL"))
      (libsource (lib "eagle-import") (part "RESISTOR0402-RES"))
    )
    (comp (ref "C501")
      (value "10u/10V")
      (footprint "eagle-import:0805-CAP")
      (fields (field (name "PARTNO") "CC0805ZKY5V6BB106"))
      (libsource (lib "eagle-import") (part "CAP0805"))
    )
    (comp (ref "C502")
      (value "10n")
      (footprint "eagle-import:0402-CAP")
      (fields (field (name "PARTNO") "CC0402KRX7R7BB103"))
      (libsource (lib "eagle-import") (part "CAP0402"))
    )
    (comp (ref "C503")
      (value "0u1")
      (footprint "eagle-import:0402-CAP")
      (fields (field (name "PARTNO") "CC0402ZRY5V7BB104"))
      (libsource (lib "eagle-import") (part "CAP0402"))
    )
    (comp (ref "U$501")
      (value "MAX21100")
      (footprint "eagle-import:16LGA-3X3")
      (fields (field (name "PARTNO") "MAX21100+"))
      (libsource (lib "eagle-import") (part "MAX21100"))
    )
    (comp (ref "D901")
      (value "DIODE-SCHOTTKY")
      (footprint "eagle-import:SOD-523")
      (fields (field (name "PARTNO") "MBRA140"))
      (libsource (lib "eagle-import") (part "DIODE-SCHOTTKY"))
    )
    (comp (ref "D902")
      (value "B340A")
      (footprint "eagle-import:SMA-DIODE")
      (libsource (lib "eagle-import") (part "DIODESMA"))
    )
    (comp (ref "D903")
      (value "B340A")
      (footprint "eagle-import:SMA-DIODE")
      (libsource (lib "eagle-import") (part "DIODESMA"))
    )
    (comp (ref "D904")
      (value "MSS1P4-M3")
      (footprint "eagle-import:MICROSMP")
      (fields (field (name "PARTNO") "MSS1P4-M3/89A"))
      (libsource (lib "eagle-import") (part "DIODE-SCHOTTKY_MSMP"))
    )
    (comp (ref "JP901")
      (value "M02PTH3")
      (footprint "eagle-import:1X02_LONGPADS")
      (libsource (lib "eagle-import") (part "M02PTH3"))
    )
    (comp (ref "R901")
      (value "10K/0.1%")
      (footprint "eagle-import:0402-RES")
      (fields (field (name "PARTNO") "ERA-2AEB103X"))
      (libsource (lib "eagle-import") (part "RESISTOR0402-RES"))
    )
    (comp (ref "R902")
      (value "10K/0.1%")
      (footprint "eagle-import:0402-RES")
      (fields (field (name "PARTNO") "ERA-2AEB103X"))
      (libsource (lib "eagle-import") (part "RESISTOR0402-RES"))
    )
    (comp (ref "R903")
      (value "10K/0.1%")
      (footprint "eagle-import:0402-RES")
      (fields (field (name "PARTNO") "ERA-2AEB103X"))
      (libsource (lib "eagle-import") (part "RESISTOR0402-RES"))
    )
    (comp (ref "JP801")
      (value "M03PTH")
      (footprint "eagle-import:1X03")
      (libsource (lib "eagle-import") (part "M03PTH"))
    )
    (comp (ref "LED801")
      (value "AMBER")
      (footprint "eagle-import:0603-LED")
      (fields (field (name "PARTNO") "APTD1608SECK"))
      (libsource (lib "eagle-import") (part "LED0603"))
    )
    (comp (ref "LED802")
      (value "GREEN")
      (footprint "eagle-import:0603-LED")
      (fields (field (name "PARTNO") "APTD1608CGCK"))
      (libsource (lib "eagle-import") (part "LED0603"))
    )
    (comp (ref "R801")
      (value "47R")
      (footprint "eagle-import:0402-RES")
      (fields (field (name "PARTNO") "RC0402JR-0747RL"))
      (libsource (lib "eagle-import") (part "RESISTOR0402-RES"))
    )
    (comp (ref "R802")
      (value "1K5")
      (footprint "eagle-import:0402-RES")
      (fields (field (name "PARTNO") "RC0402FR-071K5L"))
      (libsource (lib "eagle-import") (part "RESISTOR0402-RES"))
    )
    (comp (ref "R803")
      (value "220R")
      (footprint "eagle-import:0402-RES")
      (fields (field (name "PARTNO") "RC0402FR-07220RL"))
      (libsource (lib "eagle-import") (part "RESISTOR0402-RES"))
    )
    (comp (ref "R804")
      (value "220R")
      (footprint "eagle-import:0402-RES")
      (fields (field (name "PARTNO") "RC0402FR-07220RL"))
      (libsource (lib "eagle-import") (part "RESISTOR0402-RES"))
    )
    (comp (ref "R805")
      (value "220R")
      (footprint "eagle-import:0402-RES")
      (fields (field (name "PARTNO") "RC0402FR-07220RL"))
      (libsource (lib "eagle-import") (part "RESISTOR0402-RES"))
    )
    (comp (ref "U$801")
      (value "PESD0402-140")
      (footprint "eagle-import:0402-TVS")
      (libsource (lib "eagle-import") (part "DIODE-TVS"))
    )
    (comp (ref "C101")
      (value "16p")
      (footprint "eagle-import:0402-CAP")
      (fields (field (name "PARTNO") "C1005C0G1H160"))
      (libsource (lib "eagle-import") (part "CAP0402"))
    )
    (comp (ref "C102")
      (value "16p")
      (footprint "eagle-import:0402-CAP")
      (fields (field (name "PARTNO") "C1005C0G1H160"))
      (libsource (lib "eagle-import") (part "CAP0402"))
    )
    (comp (ref "R101")
      (value "10K")
      (footprint "eagle-import:0402-RES")
      (fields (field (name "PARTNO") "RC0402FR-0710KL"))
      (libsource (lib "eagle-import") (part "RESISTOR0402-RES"))
    )
    (comp (ref "X101")
      (value "3.2x2.5 mm / 24 MHz / 30 ppm / 10pF")
      (footprint "eagle-import:OSCILLATOR-3.2X2.5")
      (fields (field (name "PARTNO") "ABM8G-24.000MHZ-4Y-T3"))
      (libsource (lib "eagle-import") (part "OSCILLATOR-3.2X2.5"))
    )
    (comp (ref "JP1101")
      (value "FIDUCIAL1.5X3")
      (footprint "eagle-import:FIDUCIAL-1.5X3")
      (libsource (lib "eagle-import") (part "FIDUCIAL1.5X3"))
    )
    (comp (ref "JP1102")
      (value "FIDUCIAL1.5X3")
      (footprint "eagle-import:FIDUCIAL-1.5X3")
      (libsource (lib "eagle-import") (part "FIDUCIAL1.5X3"))
    )
    (comp (ref "JP1103")
      (value "FIDUCIAL1.5X3")
      (footprint "eagle-import:FIDUCIAL-1.5X3")
      (libsource (lib "eagle-import") (part "FIDUCIAL1.5X3"))
    )
    (comp (ref "JP1104")
      (value "FIDUCIAL1.5X3")
      (footprint "eagle-import:FIDUCIAL-1.5X3")
      (libsource (lib "eagle-import") (part "FIDUCIAL1.5X3"))
    )
    (comp (ref "JP1105")
      (value "M01PTH")
      (footprint "eagle-import:1X01")
      (libsource (lib "eagle-import") (part "M01PTH"))
    )
    (comp (ref "M3_MOUNT1101")
      (value "MOUNT-HOLE3.1MM")
      (footprint "eagle-import:MOUNT-HOLE3.1")
      (libsource (lib "eagle-import") (part "MOUNT-HOLE3.1MM"))
    )
    (comp (ref "M3_MOUNT1102")
      (value "MOUNT-HOLE3.1MM")
      (footprint "eagle-import:MOUNT-HOLE3.1")
      (libsource (lib "eagle-import") (part "MOUNT-HOLE3.1MM"))
    )
    (comp (ref "M3_MOUNT1103")
      (value "MOUNT-HOLE3.1MM")
      (footprint "eagle-import:MOUNT-HOLE3.1")
      (libsource (lib "eagle-import") (part "MOUNT-HOLE3.1MM"))
    )
    (comp (ref "M3_MOUNT1104")
      (value "MOUNT-HOLE3.1MM")
      (footprint "eagle-import:MOUNT-HOLE3.1")
      (libsource (lib "eagle-import") (part "MOUNT-HOLE3.1MM"))
    )
    (comp (ref "OSHW_LOGO")
      (value "OSHW-LOGOS")
      (footprint "eagle-import:OSHW-LOGO-S")
      (libsource (lib "eagle-import") (part "OSHW-LOGOS"))
    )
    (comp (ref "C401")
      (value "0u1")
      (footprint "eagle-import:0402-CAP")
      (fields (field (name "PARTNO") "CC0402ZRY5V7BB104"))
      (libsource (lib "eagle-import") (part "CAP0402"))
    )
    (comp (ref "C402")
      (value "0u1")
      (footprint "eagle-import:0402-CAP")
      (fields (field (name "PARTNO") "CC0402ZRY5V7BB104"))
      (libsource (lib "eagle-import") (part "CAP0402"))
    )
    (comp (ref "C403")
      (value "0u1")
      (footprint "eagle-import:0402-CAP")
      (fields (field (name "PARTNO") "CC0402ZRY5V7BB104"))
      (libsource (lib "eagle-import") (part "CAP0402"))
    )
    (comp (ref "C404")
      (value "0u1")
      (footprint "eagle-import:0402-CAP")
      (fields (field (name "PARTNO") "CC0402ZRY5V7BB104"))
      (libsource (lib "eagle-import") (part "CAP0402"))
    )
    (comp (ref "J401")
      (value "M04X2")
      (footprint "eagle-import:2X4")
      (libsource (lib "eagle-import") (part "M04X2"))
    )
    (comp (ref "JP401")
      (value "M04PTH")
      (footprint "eagle-import:1X04")
      (libsource (lib "eagle-import") (part "M04PTH"))
    )
    (comp (ref "JP402")
      (value "M04PTH")
      (footprint "eagle-import:1X04")
      (libsource (lib "eagle-import") (part "M04PTH"))
    )
    (comp (ref "JP403")
      (value "M03PTH")
      (footprint "eagle-import:1X03")
      (fields (field (name "PARTNO") "EXCLUDE"))
      (libsource (lib "eagle-import") (part "M03PTH"))
    )
    (comp (ref "JP404")
      (value "M04PTH")
      (footprint "eagle-import:1X04")
      (libsource (lib "eagle-import") (part "M04PTH"))
    )
    (comp (ref "JP405")
      (value "M04PTH")
      (footprint "eagle-import:1X04")
      (libsource (lib "eagle-import") (part "M04PTH"))
    )
    (comp (ref "L401")
      (value "KNH16C104DA5TS")
      (footprint "eagle-import:KYOCERA-KNH16-DA")
      (libsource (lib "eagle-import") (part "KNH16C104DA5TS"))
    )
    (comp (ref "L402")
      (value "KNH16C104DA5TS")
      (footprint "eagle-import:KYOCERA-KNH16-DA")
      (libsource (lib "eagle-import") (part "KNH16C104DA5TS"))
    )
    (comp (ref "L403")
      (value "NUF8402MN")
      (footprint "eagle-import:DFN16-THIN")
      (fields (field (name "PARTNO") "NUF8402MN"))
      (libsource (lib "eagle-import") (part "NUF8402MN"))
    )
    (comp (ref "L404")
      (value "KNH16C104DA5TS")
      (footprint "eagle-import:KYOCERA-KNH16-DA")
      (libsource (lib "eagle-import") (part "KNH16C104DA5TS"))
    )
    (comp (ref "R401")
      (value "1K5")
      (footprint "eagle-import:0402-RES")
      (fields (field (name "PARTNO") "RC0402FR-071K5L"))
      (libsource (lib "eagle-import") (part "RESISTOR0402-RES"))
    )
    (comp (ref "R402")
      (value "1K5")
      (footprint "eagle-import:0402-RES")
      (fields (field (name "PARTNO") "RC0402FR-071K5L"))
      (libsource (lib "eagle-import") (part "RESISTOR0402-RES"))
    )
    (comp (ref "R403")
      (value "1K5")
      (footprint "eagle-import:0402-RES")
      (fields (field (name "PARTNO") "RC0402FR-071K5L"))
      (libsource (lib "eagle-import") (part "RESISTOR0402-RES"))
    )
    (comp (ref "R404")
      (value "1K5")
      (footprint "eagle-import:0402-RES")
      (fields (field (name "PARTNO") "RC0402FR-071K5L"))
      (libsource (lib "eagle-import") (part "RESISTOR0402-RES"))
    )
    (comp (ref "R405")
      (value "10K/0.1%")
      (footprint "eagle-import:0402-RES")
      (fields (field (name "PARTNO") "ERA-2AEB103X"))
      (libsource (lib "eagle-import") (part "RESISTOR0402-RES"))
    )
    (comp (ref "R406")
      (value "10K/0.1%")
      (footprint "eagle-import:0402-RES")
      (fields (field (name "PARTNO") "ERA-2AEB103X"))
      (libsource (lib "eagle-import") (part "RESISTOR0402-RES"))
    )
    (comp (ref "R407")
      (value "120R")
      (footprint "eagle-import:0402-RES")
      (fields (field (name "PARTNO") "RC0402FR-07120RL"))
      (libsource (lib "eagle-import") (part "RESISTOR0402-RES"))
    )
    (comp (ref "R408")
      (value "120R")
      (footprint "eagle-import:0402-RES")
      (fields (field (name "PARTNO") "RC0402FR-07120RL"))
      (libsource (lib "eagle-import") (part "RESISTOR0402-RES"))
    )
    (comp (ref "SJ401")
      (value "SOLDERJUMPERNC2")
      (footprint "eagle-import:SJ_2S-NOTRACE")
      (libsource (lib "eagle-import") (part "SOLDERJUMPERNC2"))
    )
    (comp (ref "SJ402")
      (value "SOLDERJUMPERNC2")
      (footprint "eagle-import:SJ_2S-NOTRACE")
      (libsource (lib "eagle-import") (part "SOLDERJUMPERNC2"))
    )
    (comp (ref "U$401")
      (value "PESD0402-140")
      (footprint "eagle-import:0402-TVS")
      (libsource (lib "eagle-import") (part "DIODE-TVS"))
    )
    (comp (ref "U$402")
      (value "PESD0402-140")
      (footprint "eagle-import:0402-TVS")
      (libsource (lib "eagle-import") (part "DIODE-TVS"))
    )
    (comp (ref "U401")
      (value "MAX3051")
      (footprint "eagle-import:SOT23-8")
      (fields (field (name "PARTNO") "MAX3051EKA"))
      (libsource (lib "eagle-import") (part "MAX3051MAX3051EKA"))
    )
    (comp (ref "U402")
      (value "MAX3051")
      (footprint "eagle-import:SOT23-8")
      (fields (field (name "PARTNO") "MAX3051EKA"))
      (libsource (lib "eagle-import") (part "MAX3051MAX3051EKA"))
    )
    (comp (ref "C301")
      (value "2u2")
      (footprint "eagle-import:0603-CAP")
      (fields (field (name "PARTNO") "C1608Y5V1C225Z"))
      (libsource (lib "eagle-import") (part "CAP0603"))
    )
    (comp (ref "C302")
      (value "0u1")
      (footprint "eagle-import:0402-CAP")
      (fields (field (name "PARTNO") "CC0402ZRY5V7BB104"))
      (libsource (lib "eagle-import") (part "CAP0402"))
    )
    (comp (ref "JP301")
      (value "M04PTH")
      (footprint "eagle-import:1X04")
      (libsource (lib "eagle-import") (part "M04PTH"))
    )
    (comp (ref "JX301")
      (value "ARM_MINI_JTAG-SMT")
      (footprint "eagle-import:FTSH-105-01-XXX-DV-K")
      (fields (field (name "BOM") "EXCLUDE") (field (name "PARTNO") "M50-3900542"))
      (libsource (lib "eagle-import") (part "ARM_MINI_JTAG-SMT"))
    )
    (comp (ref "TP1")
      (value "TPTP20R")
      (footprint "eagle-import:TP20R")
      (libsource (lib "eagle-import") (part "TPTP20R"))
    )
    (comp (ref "TP2")
      (value "TPTP20R")
      (footprint "eagle-import:TP20R")
      (libsource (lib "eagle-import") (part "TPTP20R"))
    )
    (comp (ref "TP3")
      (value "TPTP20R")
      (footprint "eagle-import:TP20R")
      (libsource (lib "eagle-import") (part "TPTP20R"))
    )
    (comp (ref "TP4")
      (value "TPTP20R")
      (footprint "eagle-import:TP20R")
      (libsource (lib "eagle-import") (part "TPTP20R"))
    )
    (comp (ref "TP5")
      (value "TPTP20R")
      (footprint "eagle-import:TP20R")
      (libsource (lib "eagle-import") (part "TPTP20R"))
    )
    (comp (ref "U$301")
      (value "NUF2042XV6")
      (footprint "eagle-import:SOT563-6")
      (libsource (lib "eagle-import") (part "NUF2042XV6"))
    )
    (comp (ref "U$302")
      (value "W25Q64FV")
      (footprint "eagle-import:WSON-8-5X6")
      (fields (field (name "PARTNO") "W25Q64FVZP"))
      (libsource (lib "eagle-import") (part "W25Q64FV"))
    )
  )
  (nets
    (net (code "1") (name "ACCEL_DRDY") (class "Default")
      (node (ref "U$501") (pin "11") (pinfunction "INT1_11") (pintype "bidirectional"))
      (node (ref "U101") (pin "90") (pinfunction "PB4_90") (pintype "bidirectional"))
    )
    (net (code "2") (name "ALARM") (class "Default")
      (node (ref "U101") (pin "77") (pinfunction "PA15_77") (pintype "bidirectional"))
    )
    (net (code "3") (name "CAN1_H") (class "Default")
      (node (ref "JP405") (pin "2") (pinfunction "2_2") (pintype "passive"))
      (node (ref "R407") (pin "P$1") (pinfunction "1_P$1") (pintype "passive"))
      (node (ref "U402") (pin "7") (pinfunction "CANH_7") (pintype "bidirectional"))
    )
    (net (code "4") (name "CAN1_L") (class "Default")
      (node (ref "JP405") (pin "3") (pinfunction "3_3") (pintype "passive"))
      (node (ref "SJ402") (pin "2") (pinfunction "2_2") (pintype "passive"))
      (node (ref "U402") (pin "6") (pinfunction "CANL_6") (pintype "bidirectional"))
    )
    (net (code "5") (name "CAN1_RX") (class "Default")
      (node (ref "U101") (pin "81") (pinfunction "PD0_81") (pintype "bidirectional"))
      (node (ref "U402") (pin "4") (pinfunction "DOUT_4") (pintype "output"))
    )
    (net (code "6") (name "CAN1_TX") (class "Default")
      (node (ref "U101") (pin "82") (pinfunction "PD1_82") (pintype "bidirectional"))
      (node (ref "U402") (pin "1") (pinfunction "DIN_1") (pintype "input"))
    )
    (net (code "7") (name "CAN2_RX") (class "Default")
      (node (ref "U101") (pin "51") (pinfunction "PB12_51") (pintype "bidirectional"))
      (node (ref "U401") (pin "4") (pinfunction "DOUT_4") (pintype "output"))
    )
    (net (code "8") (name "CAN2_TX") (class "Default")
      (node (ref "U101") (pin "92") (pinfunction "PB6_92") (pintype "bidirectional"))
      (node (ref "U401") (pin "1") (pinfunction "DIN_1") (pintype "input"))
    )
    (net (code "9") (name "FMU-BOOT0") (class "Default")
      (node (ref "JP1105") (pin "1") (pinfunction "1_1") (pintype "passive"))
      (node (ref "R709") (pin "P$2") (pinfunction "2_P$2") (pintype "passive"))
      (node (ref "U101") (pin "94") (pinfunction "BOOT0_94") (pintype "input"))
    )
    (net (code "10") (name "FMU-CH1") (class "Default")
      (node (ref "L1001") (pin "P$4") (pinfunction "P$1_P$4") (pintype "bidirectional"))
      (node (ref "U101") (pin "45") (pinfunction "PE14_45") (pintype "bidirectional"))
    )
    (net (code "11") (name "FMU-CH2") (class "Default")
      (node (ref "L1001") (pin "P$5") (pinfunction "P$1_P$5") (pintype "bidirectional"))
      (node (ref "U101") (pin "44") (pinfunction "PE13_44") (pintype "bidirectional"))
    )
    (net (code "12") (name "FMU-CH3") (class "Default")
      (node (ref "L1001") (pin "P$6") (pinfunction "P$1_P$6") (pintype "bidirectional"))
      (node (ref "U101") (pin "42") (pinfunction "PE11_42") (pintype "bidirectional"))
    )
    (net (code "13") (name "FMU-CH4") (class "Default")
      (node (ref "L1001") (pin "P$7") (pinfunction "P$1_P$7") (pintype "bidirectional"))
      (node (ref "U101") (pin "40") (pinfunction "PE9_40") (pintype "bidirectional"))
    )
    (net (code "14") (name "FMU-CH5") (class "Default")
      (node (ref "L1001") (pin "P$2") (pinfunction "P$1_P$2") (pintype "bidirectional"))
      (node (ref "U101") (pin "60") (pinfunction "PD13_60") (pintype "bidirectional"))
    )
    (net (code "15") (name "FMU-CH6") (class "Default")
      (node (ref "L1001") (pin "P$3") (pinfunction "P$1_P$3") (pintype "bidirectional"))
      (node (ref "U101") (pin "62") (pinfunction "PD15_62") (pintype "bidirectional"))
    )
    (net (code "16") (name "FMU-CH7") (class "Default")
      (node (ref "L1001") (pin "P$8") (pinfunction "P$1_P$8") (pintype "bidirectional"))
      (node (ref "U101") (pin "24") (pinfunction "PA1_24") (pintype "bidirectional"))
    )
    (net (code "17") (name "FMU-CH8") (class "Default")
      (node (ref "L1001") (pin "P$1") (pinfunction "P$1_P$1") (pintype "bidirectional"))
      (node (ref "U$203") (pin "3") (pinfunction "2Y_3") (pintype "bidirectional"))
      (node (ref "U101") (pin "61") (pinfunction "PD14_61") (pintype "bidirectional"))
    )
    (net (code "18") (name "FMU-CH9") (class "Default")
      (node (ref "R1001") (pin "P$2") (pinfunction "2_P$2") (pintype "passive"))
      (node (ref "U101") (pin "25") (pinfunction "PA2_25") (pintype "bidirectional"))
    )
    (net (code "19") (name "FMU-CH10") (class "Default")
      (node (ref "R1002") (pin "P$2") (pinfunction "2_P$2") (pintype "passive"))
      (node (ref "U101") (pin "26") (pinfunction "PA3_26") (pintype "bidirectional"))
    )
    (net (code "20") (name "FMU-I2C1_SCL") (class "Default")
      (node (ref "L403") (pin "P$2") (pinfunction "P$1_P$2") (pintype "bidirectional"))
      (node (ref "R402") (pin "P$1") (pinfunction "1_P$1") (pintype "passive"))
      (node (ref "U101") (pin "95") (pinfunction "PB8_95") (pintype "bidirectional"))
    )
    (net (code "21") (name "FMU-I2C1_SDA") (class "Default")
      (node (ref "L403") (pin "P$7") (pinfunction "P$1_P$7") (pintype "bidirectional"))
      (node (ref "R404") (pin "P$1") (pinfunction "1_P$1") (pintype "passive"))
      (node (ref "U101") (pin "96") (pinfunction "PB9_96") (pintype "bidirectional"))
    )
    (net (code "22") (name "FMU-I2C2_SCL") (class "Default")
      (node (ref "L403") (pin "P$4") (pinfunction "P$1_P$4") (pintype "bidirectional"))
      (node (ref "R401") (pin "P$1") (pinfunction "1_P$1") (pintype "passive"))
      (node (ref "U101") (pin "47") (pinfunction "PB10_47") (pintype "bidirectional"))
    )
    (net (code "23") (name "FMU-I2C2_SDA") (class "Default")
      (node (ref "L403") (pin "P$8") (pinfunction "P$1_P$8") (pintype "bidirectional"))
      (node (ref "R403") (pin "P$1") (pinfunction "1_P$1") (pintype "passive"))
      (node (ref "U101") (pin "48") (pinfunction "PB11_48") (pintype "bidirectional"))
    )
    (net (code "24") (name "FMU-LED_SAFETY") (class "Default")
      (node (ref "R801") (pin "P$2") (pinfunction "2_P$2") (pintype "passive"))
      (node (ref "U101") (pin "9") (pinfunction "PC15_9") (pintype "bidirectional"))
    )
    (net (code "25") (name "FMU-SWCLK") (class "Default")
      (node (ref "JX301") (pin "4") (pinfunction "S_4") (pintype "passive"))
      (node (ref "TP2") (pin "TP") (pinfunction "TP_TP") (pintype "input"))
      (node (ref "U101") (pin "76") (pinfunction "PA14_76") (pintype "bidirectional"))
    )
    (net (code "26") (name "FMU-SWDIO") (class "Default")
      (node (ref "JX301") (pin "2") (pinfunction "S_2") (pintype "passive"))
      (node (ref "TP1") (pin "TP") (pinfunction "TP_TP") (pintype "input"))
      (node (ref "U101") (pin "72") (pinfunction "PA13_72") (pintype "bidirectional"))
    )
    (net (code "27") (name "FMU-SWO") (class "Default")
      (node (ref "JX301") (pin "6") (pinfunction "S_6") (pintype "passive"))
      (node (ref "TP3") (pin "TP") (pinfunction "TP_TP") (pintype "input"))
      (node (ref "U101") (pin "89") (pinfunction "PB3_89") (pintype "bidirectional"))
    )
    (net (code "28") (name "FMU-UART7_RX") (class "Default")
      (node (ref "L202") (pin "P$8") (pinfunction "P$1_P$8") (pintype "bidirectional"))
      (node (ref "U101") (pin "38") (pinfunction "PE7_38") (pintype "bidirectional"))
    )
    (net (code "29") (name "FMU-UART7_TX") (class "Default")
      (node (ref "L202") (pin "P$6") (pinfunction "P$1_P$6") (pintype "bidirectional"))
      (node (ref "U101") (pin "39") (pinfunction "PE8_39") (pintype "bidirectional"))
    )
    (net (code "30") (name "FMU-UART8_RX") (class "Default")
      (node (ref "U$203") (pin "6") (pinfunction "1Y_6") (pintype "bidirectional"))
      (node (ref "U101") (pin "97") (pinfunction "PE0_97") (pintype "bidirectional"))
    )
    (net (code "31") (name "FMU-UART8_TX") (class "Default")
      (node (ref "U$203") (pin "5") (pinfunction "2A_5") (pintype "bidirectional"))
      (node (ref "U101") (pin "98") (pinfunction "PE1_98") (pintype "bidirectional"))
    )
    (net (code "32") (name "FMU-USART2_CTS") (class "Default")
      (node (ref "L201") (pin "P$1") (pinfunction "P$1_P$1") (pintype "bidirectional"))
      (node (ref "U101") (pin "84") (pinfunction "PD3_84") (pintype "bidirectional"))
    )
    (net (code "33") (name "FMU-USART2_RTS") (class "Default")
      (node (ref "L201") (pin "P$2") (pinfunction "P$1_P$2") (pintype "bidirectional"))
      (node (ref "U101") (pin "85") (pinfunction "PD4_85") (pintype "bidirectional"))
    )
    (net (code "34") (name "FMU-USART2_RX") (class "Default")
      (node (ref "L201") (pin "P$4") (pinfunction "P$1_P$4") (pintype "bidirectional"))
      (node (ref "U101") (pin "87") (pinfunction "PD6_87") (pintype "bidirectional"))
    )
    (net (code "35") (name "FMU-USART2_TX") (class "Default")
      (node (ref "L201") (pin "P$3") (pinfunction "P$1_P$3") (pintype "bidirectional"))
      (node (ref "U101") (pin "86") (pinfunction "PD5_86") (pintype "bidirectional"))
    )
    (net (code "36") (name "FMU-USART3_CTS") (class "Default")
      (node (ref "L201") (pin "P$7") (pinfunction "P$1_P$7") (pintype "bidirectional"))
      (node (ref "U101") (pin "58") (pinfunction "PD11_58") (pintype "bidirectional"))
    )
    (net (code "37") (name "FMU-USART3_RTS") (class "Default")
      (node (ref "L201") (pin "P$8") (pinfunction "P$1_P$8") (pintype "bidirectional"))
      (node (ref "U101") (pin "59") (pinfunction "PD12_59") (pintype "bidirectional"))
    )
    (net (code "38") (name "FMU-USART3_RX") (class "Default")
      (node (ref "L201") (pin "P$6") (pinfunction "P$1_P$6") (pintype "bidirectional"))
      (node (ref "U101") (pin "56") (pinfunction "PD9_56") (pintype "bidirectional"))
    )
    (net (code "39") (name "FMU-USART3_TX") (class "Default")
      (node (ref "L201") (pin "P$5") (pinfunction "P$1_P$5") (pintype "bidirectional"))
      (node (ref "U101") (pin "55") (pinfunction "PD8_55") (pintype "bidirectional"))
    )
    (net (code "40") (name "FMU-VDD_3V3") (class "Default")
      (node (ref "C201") (pin "P$1") (pinfunction "1_P$1") (pintype "passive"))
      (node (ref "C301") (pin "P$1") (pinfunction "1_P$1") (pintype "passive"))
      (node (ref "C302") (pin "P$1") (pinfunction "1_P$1") (pintype "passive"))
      (node (ref "C401") (pin "P$1") (pinfunction "1_P$1") (pintype "passive"))
      (node (ref "C402") (pin "P$1") (pinfunction "1_P$1") (pintype "passive"))
      (node (ref "C705") (pin "P$1") (pinfunction "1_P$1") (pintype "passive"))
      (node (ref "C706") (pin "P$1") (pinfunction "1_P$1") (pintype "passive"))
      (node (ref "C709") (pin "P$1") (pinfunction "1_P$1") (pintype "passive"))
      (node (ref "C710") (pin "P$1") (pinfunction "1_P$1") (pintype "passive"))
      (node (ref "C711") (pin "P$1") (pinfunction "1_P$1") (pintype "passive"))
      (node (ref "C712") (pin "P$1") (pinfunction "1_P$1") (pintype "passive"))
      (node (ref "C714") (pin "P$1") (pinfunction "1_P$1") (pintype "passive"))
      (node (ref "C716") (pin "P$1") (pinfunction "1_P$1") (pintype "passive"))
      (node (ref "D701") (pin "A") (pinfunction "A_A") (pintype "passive"))
      (node (ref "JP801") (pin "1") (pinfunction "1_1") (pintype "passive"))
      (node (ref "JX301") (pin "1") (pinfunction "S_1") (pintype "passive"))
      (node (ref "R401") (pin "P$2") (pinfunction "2_P$2") (pintype "passive"))
      (node (ref "R402") (pin "P$2") (pinfunction "2_P$2") (pintype "passive"))
      (node (ref "R403") (pin "P$2") (pinfunction "2_P$2") (pintype "passive"))
      (node (ref "R404") (pin "P$2") (pinfunction "2_P$2") (pintype "passive"))
      (node (ref "R702") (pin "P$1") (pinfunction "1_P$1") (pintype "passive"))
      (node (ref "R704") (pin "P$1") (pinfunction "1_P$1") (pintype "passive"))
      (node (ref "R705") (pin "P$1") (pinfunction "1_P$1") (pintype "passive"))
      (node (ref "TP5") (pin "TP") (pinfunction "TP_TP") (pintype "input"))
      (node (ref "U$203") (pin "8") (pinfunction "VCC_8") (pintype "power_in"))
      (node (ref "U$302") (pin "8") (pinfunction "VCC_8") (pintype "bidirectional"))
      (node (ref "U$701") (pin "7") (pinfunction "VOUT2_7") (pintype "bidirectional"))
      (node (ref "U$801") (pin "C") (pinfunction "C_C") (pintype "passive"))
      (node (ref "U101") (pin "100") (pinfunction "VDD_100") (pintype "power_in"))
      (node (ref "U101") (pin "11") (pinfunction "VDD_11") (pintype "power_in"))
      (node (ref "U101") (pin "19") (pinfunction "VDD_19") (pintype "power_in"))
      (node (ref "U101") (pin "21") (pinfunction "VREF+_21") (pintype "input"))
      (node (ref "U101") (pin "22") (pinfunction "VDDA_22") (pintype "power_in"))
      (node (ref "U101") (pin "28") (pinfunction "VDD_28") (pintype "power_in"))
      (node (ref "U101") (pin "50") (pinfunction "VDD_50") (pintype "power_in"))
      (node (ref "U101") (pin "75") (pinfunction "VDD_75") (pintype "power_in"))
      (node (ref "U401") (pin "3") (pinfunction "VCC_3") (pintype "input"))
      (node (ref "U402") (pin "3") (pinfunction "VCC_3") (pintype "input"))
    )
    (net (code "41") (name "FMU-~{RESET}") (class "Default")
      (node (ref "C713") (pin "P$2") (pinfunction "2_P$2") (pintype "passive"))
      (node (ref "JX301") (pin "10") (pinfunction "S_10") (pintype "passive"))
      (node (ref "S701") (pin "A1") (pinfunction "1_A1") (pintype "passive"))
      (node (ref "TP4") (pin "TP") (pinfunction "TP_TP") (pintype "input"))
      (node (ref "U$701") (pin "3") (pinfunction "POR2_3") (pintype "bidirectional"))
      (node (ref "U101") (pin "14") (pinfunction "NRST_14") (pintype "input"))
    )
    (net (code "42") (name "FMU_AUX_ADC1") (class "Default")
      (node (ref "R405") (pin "P$1") (pinfunction "1_P$1") (pintype "passive"))
      (node (ref "U101") (pin "18") (pinfunction "PC3_18") (pintype "bidirectional"))
    )
    (net (code "43") (name "FMU_AUX_ADC2") (class "Default")
      (node (ref "R406") (pin "P$1") (pinfunction "1_P$1") (pintype "passive"))
      (node (ref "U101") (pin "33") (pinfunction "PC4_33") (pintype "bidirectional"))
    )
    (net (code "44") (name "FRAM_MISO") (class "Default")
      (node (ref "U101") (pin "53") (pinfunction "PB14_53") (pintype "bidirectional"))
    )
    (net (code "45") (name "FRAM_MOSI") (class "Default")
      (node (ref "U101") (pin "54") (pinfunction "PB15_54") (pintype "bidirectional"))
    )
    (net (code "46") (name "FRAM_SCK") (class "Default")
      (node (ref "U101") (pin "52") (pinfunction "PB13_52") (pintype "bidirectional"))
    )
    (net (code "47") (name "GND") (class "Default")
      (node (ref "C101") (pin "P$2") (pinfunction "2_P$2") (pintype "passive"))
      (node (ref "C102") (pin "P$1") (pinfunction "1_P$1") (pintype "passive"))
      (node (ref "C201") (pin "P$2") (pinfunction "2_P$2") (pintype "passive"))
      (node (ref "C301") (pin "P$2") (pinfunction "2_P$2") (pintype "passive"))
      (node (ref "C302") (pin "P$2") (pinfunction "2_P$2") (pintype "passive"))
      (node (ref "C401") (pin "P$2") (pinfunction "2_P$2") (pintype "passive"))
      (node (ref "C402") (pin "P$2") (pinfunction "2_P$2") (pintype "passive"))
      (node (ref "C403") (pin "P$2") (pinfunction "2_P$2") (pintype "passive"))
      (node (ref "C404") (pin "P$2") (pinfunction "2_P$2") (pintype "passive"))
      (node (ref "C501") (pin "P$2") (pinfunction "2_P$2") (pintype "passive"))
      (node (ref "C502") (pin "P$2") (pinfunction "2_P$2") (pintype "passive"))
      (node (ref "C503") (pin "P$2") (pinfunction "2_P$2") (pintype "passive"))
      (node (ref "C601") (pin "2") (pinfunction "2_2") (pintype "passive"))
      (node (ref "C602") (pin "P$2") (pinfunction "2_P$2") (pintype "passive"))
      (node (ref "C603") (pin "P$2") (pinfunction "2_P$2") (pintype "passive"))
      (node (ref "C604") (pin "2") (pinfunction "2_2") (pintype "passive"))
      (node (ref "C605") (pin "2") (pinfunction "2_2") (pintype "passive"))
      (node (ref "C606") (pin "2") (pinfunction "2_2") (pintype "passive"))
      (node (ref "C701") (pin "P$2") (pinfunction "2_P$2") (pintype "passive"))
      (node (ref "C702") (pin "P$2") (pinfunction "2_P$2") (pintype "passive"))
      (node (ref "C703") (pin "P$1") (pinfunction "1_P$1") (pintype "passive"))
      (node (ref "C704") (pin "P$2") (pinfunction "2_P$2") (pintype "passive"))
      (node (ref "C705") (pin "P$2") (pinfunction "2_P$2") (pintype "passive"))
      (node (ref "C706") (pin "P$2") (pinfunction "2_P$2") (pintype "passive"))
      (node (ref "C707") (pin "P$2") (pinfunction "2_P$2") (pintype "passive"))
      (node (ref "C708") (pin "P$2") (pinfunction "2_P$2") (pintype "passive"))
      (node (ref "C709") (pin "P$2") (pinfunction "2_P$2") (pintype "passive"))
      (node (ref "C710") (pin "P$2") (pinfunction "2_P$2") (pintype "passive"))
      (node (ref "C711") (pin "P$2") (pinfunction "2_P$2") (pintype "passive"))
      (node (ref "C712") (pin "P$2") (pinfunction "2_P$2") (pintype "passive"))
      (node (ref "C713") (pin "P$1") (pinfunction "1_P$1") (pintype "passive"))
      (node (ref "C714") (pin "P$2") (pinfunction "2_P$2") (pintype "passive"))
      (node (ref "C715") (pin "P$2") (pinfunction "2_P$2") (pintype "passive"))
      (node (ref "C716") (pin "P$2") (pinfunction "2_P$2") (pintype "passive"))
      (node (ref "C717") (pin "P$2") (pinfunction "2_P$2") (pintype "passive"))
      (node (ref "D901") (pin "A") (pinfunction "A_A") (pintype "passive"))
      (node (ref "J1001") (pin "GND_S1") (pinfunction "S_GND_S1") (pintype "passive"))
      (node (ref "J1001") (pin "GND_S2") (pinfunction "S_GND_S2") (pintype "passive"))
      (node (ref "J1001") (pin "GND_S3") (pinfunction "S_GND_S3") (pintype "passive"))
      (node (ref "J1001") (pin "GND_S4") (pinfunction "S_GND_S4") (pintype "passive"))
      (node (ref "J1001") (pin "GND_S5") (pinfunction "S_GND_S5") (pintype "passive"))
      (node (ref "J1001") (pin "GND_S6") (pinfunction "S_GND_S6") (pintype "passive"))
      (node (ref "J1001") (pin "GND_S7") (pinfunction "S_GND_S7") (pintype "passive"))
      (node (ref "J1001") (pin "GND_S8") (pinfunction "S_GND_S8") (pintype "passive"))
      (node (ref "J401") (pin "7") (pinfunction "7_7") (pintype "passive"))
      (node (ref "JP202") (pin "3") (pinfunction "3_3") (pintype "bidirectional"))
      (node (ref "JP203") (pin "5") (pinfunction "5_5") (pintype "bidirectional"))
      (node (ref "JP204") (pin "5") (pinfunction "5_5") (pintype "bidirectional"))
      (node (ref "JP205") (pin "5") (pinfunction "5_5") (pintype "bidirectional"))
      (node (ref "JP301") (pin "4") (pinfunction "4_4") (pintype "passive"))
      (node (ref "JP401") (pin "4") (pinfunction "4_4") (pintype "passive"))
      (node (ref "JP402") (pin "4") (pinfunction "4_4") (pintype "passive"))
      (node (ref "JP403") (pin "3") (pinfunction "3_3") (pintype "passive"))
      (node (ref "JP404") (pin "4") (pinfunction "4_4") (pintype "passive"))
      (node (ref "JP405") (pin "4") (pinfunction "4_4") (pintype "passive"))
      (node (ref "JP901") (pin "2") (pinfunction "2_2") (pintype "passive"))
      (node (ref "JX301") (pin "3") (pinfunction "S_3") (pintype "passive"))
      (node (ref "JX301") (pin "5") (pinfunction "S_5") (pintype "passive"))
      (node (ref "JX301") (pin "9") (pinfunction "S_9") (pintype "passive"))
      (node (ref "L1001") (pin "P$EP") (pinfunction "GND_P$EP") (pintype "power_in"))
      (node (ref "L201") (pin "P$EP") (pinfunction "GND_P$EP") (pintype "power_in"))
      (node (ref "L202") (pin "P$EP") (pinfunction "GND_P$EP") (pintype "power_in"))
      (node (ref "L203") (pin "P$3") (pinfunction "P$3_P$3") (pintype "bidirectional"))
      (node (ref "L203") (pin "P$4") (pinfunction "P$3_P$4") (pintype "bidirectional"))
      (node (ref "L203") (pin "P$5") (pinfunction "P$3_P$5") (pintype "bidirectional"))
      (node (ref "L401") (pin "P$3") (pinfunction "P$3_P$3") (pintype "bidirectional"))
      (node (ref "L401") (pin "P$4") (pinfunction "P$3_P$4") (pintype "bidirectional"))
      (node (ref "L401") (pin "P$5") (pinfunction "P$3_P$5") (pintype "bidirectional"))
      (node (ref "L402") (pin "P$3") (pinfunction "P$3_P$3") (pintype "bidirectional"))
      (node (ref "L402") (pin "P$4") (pinfunction "P$3_P$4") (pintype "bidirectional"))
      (node (ref "L402") (pin "P$5") (pinfunction "P$3_P$5") (pintype "bidirectional"))
      (node (ref "L403") (pin "P$1") (pinfunction "P$1_P$1") (pintype "bidirectional"))
      (node (ref "L403") (pin "P$11") (pinfunction "P$2_P$11") (pintype "bidirectional"))
      (node (ref "L403") (pin "P$12") (pinfunction "P$2_P$12") (pintype "bidirectional"))
      (node (ref "L403") (pin "P$14") (pinfunction "P$2_P$14") (pintype "bidirectional"))
      (node (ref "L403") (pin "P$16") (pinfunction "P$2_P$16") (pintype "bidirectional"))
      (node (ref "L403") (pin "P$3") (pinfunction "P$1_P$3") (pintype "bidirectional"))
      (node (ref "L403") (pin "P$5") (pinfunction "P$1_P$5") (pintype "bidirectional"))
      (node (ref "L403") (pin "P$6") (pinfunction "P$1_P$6") (pintype "bidirectional"))
      (node (ref "L403") (pin "P$EP") (pinfunction "GND_P$EP") (pintype "power_in"))
      (node (ref "L404") (pin "P$3") (pinfunction "P$3_P$3") (pintype "bidirectional"))
      (node (ref "L404") (pin "P$4") (pinfunction "P$3_P$4") (pintype "bidirectional"))
      (node (ref "L404") (pin "P$5") (pinfunction "P$3_P$5") (pintype "bidirectional"))
      (node (ref "R101") (pin "P$2") (pinfunction "2_P$2") (pintype "passive"))
      (node (ref "R203") (pin "P$2") (pinfunction "2_P$2") (pintype "passive"))
      (node (ref "R204") (pin "P$1") (pinfunction "1_P$1") (pintype "passive"))
      (node (ref "R701") (pin "P$1") (pinfunction "1_P$1") (pintype "passive"))
      (node (ref "R703") (pin "P$2") (pinfunction "2_P$2") (pintype "passive"))
      (node (ref "R708") (pin "P$2") (pinfunction "2_P$2") (pintype "passive"))
      (node (ref "R709") (pin "P$1") (pinfunction "1_P$1") (pintype "passive"))
      (node (ref "R802") (pin "P$2") (pinfunction "2_P$2") (pintype "passive"))
      (node (ref "R805") (pin "P$1") (pinfunction "1_P$1") (pintype "passive"))
      (node (ref "R903") (pin "P$1") (pinfunction "1_P$1") (pintype "passive"))
      (node (ref "S701") (pin "B3") (pinfunction "2_B3") (pintype "passive"))
      (node (ref "U$201") (pin "A") (pinfunction "A_A") (pintype "passive"))
      (node (ref "U$202") (pin "A") (pinfunction "A_A") (pintype "passive"))
      (node (ref "U$203") (pin "1") (pinfunction "~{1OE}_1") (pintype "input"))
      (node (ref "U$203") (pin "4") (pinfunction "GND_4") (pintype "power_in"))
      (node (ref "U$204") (pin "A") (pinfunction "A_A") (pintype "passive"))
      (node (ref "U$301") (pin "2") (pinfunction "GND_2") (pintype "bidirectional"))
      (node (ref "U$302") (pin "4") (pinfunction "GND_4") (pintype "bidirectional"))
      (node (ref "U$302") (pin "PAD") (pinfunction "GND_PAD") (pintype "bidirectional"))
      (node (ref "U$401") (pin "A") (pinfunction "A_A") (pintype "passive"))
      (node (ref "U$402") (pin "A") (pinfunction "A_A") (pintype "passive"))
      (node (ref "U$501") (pin "10") (pinfunction "RSV1_10") (pintype "input"))
      (node (ref "U$501") (pin "5") (pinfunction "GND_5") (pintype "power_in"))
      (node (ref "U$601") (pin "11") (pinfunction "GND_11") (pintype "power_in"))
      (node (ref "U$601") (pin "15") (pinfunction "PGND_15") (pintype "power_in"))
      (node (ref "U$601") (pin "16") (pinfunction "PGND_16") (pintype "power_in"))
      (node (ref "U$601") (pin "17") (pinfunction "PGND_17") (pintype "power_in"))
      (node (ref "U$601") (pin "18") (pinfunction "PGND_18") (pintype "power_in"))
      (node (ref "U$601") (pin "19") (pinfunction "PGND_19") (pintype "power_in"))
      (node (ref "U$601") (pin "20") (pinfunction "PGND_20") (pintype "power_in"))
      (node (ref "U$601") (pin "21") (pinfunction "PGND_21") (pintype "power_in"))
      (node (ref "U$601") (pin "22") (pinfunction "PGND_22") (pintype "power_in"))
      (node (ref "U$601") (pin "23") (pinfunction "PGND_23") (pintype "power_in"))
      (node (ref "U$601") (pin "4") (pinfunction "PS/SYNC_4") (pintype "input"))
      (node (ref "U$601") (pin "6") (pinfunction "PGND_6") (pintype "power_in"))
      (node (ref "U$601") (pin "7") (pinfunction "PGND_7") (pintype "power_in"))
      (node (ref "U$601") (pin "8") (pinfunction "PGND_8") (pintype "power_in"))
      (node (ref "U$601") (pin "9") (pinfunction "PGND_9") (pintype "power_in"))
      (node (ref "U$601") (pin "EP") (pinfunction "PGND_EP") (pintype "power_in"))
      (node (ref "U$601") (pin "EP1") (pinfunction "PGND_EP1") (pintype "power_in"))
      (node (ref "U$701") (pin "2") (pinfunction "GND_2") (pintype "bidirectional"))
      (node (ref "U$701") (pin "GND") (pinfunction "GND_GND") (pintype "bidirectional"))
      (node (ref "U$702") (pin "2") (pinfunction "GND_2") (pintype "bidirectional"))
      (node (ref "U$702") (pin "4") (pinfunction "EN2_4") (pintype "bidirectional"))
      (node (ref "U$702") (pin "GND") (pinfunction "GND_GND") (pintype "bidirectional"))
      (node (ref "U$703") (pin "2") (pinfunction "VSS_2") (pintype "bidirectional"))
      (node (ref "U$703") (pin "6") (pinfunction "VBAT_6") (pintype "bidirectional"))
      (node (ref "U$703") (pin "GND") (pinfunction "VSS_GND") (pintype "bidirectional"))
      (node (ref "U$703") (pin "P$2") (pinfunction "VSS_P$2") (pintype "bidirectional"))
      (node (ref "U$703") (pin "P$3") (pinfunction "VSS_P$3") (pintype "bidirectional"))
      (node (ref "U$704") (pin "2") (pinfunction "NEG_2") (pintype "bidirectional"))
      (node (ref "U$801") (pin "A") (pinfunction "A_A") (pintype "passive"))
      (node (ref "U101") (pin "10") (pinfunction "VSS_10") (pintype "power_in"))
      (node (ref "U101") (pin "20") (pinfunction "VSSA_20") (pintype "power_in"))
      (node (ref "U101") (pin "27") (pinfunction "VSS_27") (pintype "power_in"))
      (node (ref "U101") (pin "74") (pinfunction "VSS_74") (pintype "power_in"))
      (node (ref "U101") (pin "99") (pinfunction "VSS_99") (pintype "power_in"))
      (node (ref "U401") (pin "2") (pinfunction "GND_2") (pintype "power_in"))
      (node (ref "U401") (pin "5") (pinfunction "SHDN_5") (pintype "input"))
      (node (ref "U401") (pin "8") (pinfunction "RS_8") (pintype "input"))
      (node (ref "U402") (pin "2") (pinfunction "GND_2") (pintype "power_in"))
      (node (ref "U402") (pin "5") (pinfunction "SHDN_5") (pintype "input"))
      (node (ref "U402") (pin "8") (pinfunction "RS_8") (pintype "input"))
      (node (ref "X101") (pin "2") (pinfunction "NC_2_2") (pintype "power_in"))
      (node (ref "X101") (pin "4") (pinfunction "NC_4_4") (pintype "power_in"))
    )
    (net (code "48") (name "GPIO_EXT_1") (class "Default")
      (node (ref "J401") (pin "5") (pinfunction "5_5") (pintype "passive"))
      (node (ref "U101") (pin "8") (pinfunction "PC14_8") (pintype "bidirectional"))
    )
    (net (code "49") (name "GYRO_DRDY") (class "Default")
      (node (ref "U$501") (pin "9") (pinfunction "INT2_9") (pintype "bidirectional"))
      (node (ref "U101") (pin "35") (pinfunction "PB0_35") (pintype "bidirectional"))
    )
    (net (code "50") (name "IO-~{RESET}") (class "Default")
      (node (ref "U$702") (pin "3") (pinfunction "POR2_3") (pintype "bidirectional"))
    )
    (net (code "51") (name "MAG_DRDY") (class "Default")
      (node (ref "U$501") (pin "12") (pinfunction "DSYNC_12") (pintype "bidirectional"))
      (node (ref "U101") (pin "36") (pinfunction "PB1_36") (pintype "bidirectional"))
    )
    (net (code "52") (name "Net-(C101-1)") (class "Default")
      (node (ref "C101") (pin "P$1") (pinfunction "1_P$1") (pintype "passive"))
      (node (ref "U101") (pin "12") (pinfunction "OSC_IN_12") (pintype "input"))
      (node (ref "X101") (pin "3") (pinfunction "3_3") (pintype "bidirectional"))
    )
    (net (code "53") (name "Net-(C102-2)") (class "Default")
      (node (ref "C102") (pin "P$2") (pinfunction "2_P$2") (pintype "passive"))
      (node (ref "U101") (pin "13") (pinfunction "OSC_OUT_13") (pintype "output"))
      (node (ref "X101") (pin "1") (pinfunction "1_1") (pintype "bidirectional"))
    )
    (net (code "54") (name "Net-(C403-1)") (class "Default")
      (node (ref "C403") (pin "P$1") (pinfunction "1_P$1") (pintype "passive"))
      (node (ref "JP403") (pin "2") (pinfunction "2_2") (pintype "passive"))
      (node (ref "R405") (pin "P$2") (pinfunction "2_P$2") (pintype "passive"))
    )
    (net (code "55") (name "Net-(C404-1)") (class "Default")
      (node (ref "C404") (pin "P$1") (pinfunction "1_P$1") (pintype "passive"))
      (node (ref "JP403") (pin "1") (pinfunction "1_1") (pintype "passive"))
      (node (ref "R406") (pin "P$2") (pinfunction "2_P$2") (pintype "passive"))
    )
    (net (code "56") (name "Net-(C503-1)") (class "Default")
      (node (ref "C503") (pin "P$1") (pinfunction "1_P$1") (pintype "passive"))
      (node (ref "U$501") (pin "13") (pinfunction "REGD_13") (pintype "power_in"))
    )
    (net (code "57") (name "Net-(C603-1)") (class "Default")
      (node (ref "C603") (pin "P$1") (pinfunction "1_P$1") (pintype "passive"))
      (node (ref "U$601") (pin "10") (pinfunction "VAUX_10") (pintype "input"))
    )
    (net (code "58") (name "Net-(C703-2)") (class "Default")
      (node (ref "C703") (pin "P$2") (pinfunction "2_P$2") (pintype "passive"))
      (node (ref "U$701") (pin "6") (pinfunction "CSET_6") (pintype "bidirectional"))
    )
    (net (code "59") (name "Net-(C704-1)") (class "Default")
      (node (ref "C704") (pin "P$1") (pinfunction "1_P$1") (pintype "passive"))
      (node (ref "U$702") (pin "6") (pinfunction "CSET_6") (pintype "bidirectional"))
    )
    (net (code "60") (name "Net-(C715-1)") (class "Default")
      (node (ref "C715") (pin "P$1") (pinfunction "1_P$1") (pintype "passive"))
      (node (ref "U101") (pin "49") (pinfunction "VCAP_1_49") (pintype "power_in"))
    )
    (net (code "61") (name "Net-(C717-1)") (class "Default")
      (node (ref "C717") (pin "P$1") (pinfunction "1_P$1") (pintype "passive"))
      (node (ref "U101") (pin "73") (pinfunction "VCAP_2_73") (pintype "power_in"))
    )
    (net (code "62") (name "Net-(J401-Pad8)") (class "Default")
      (node (ref "J401") (pin "8") (pinfunction "8_8") (pintype "passive"))
      (node (ref "L401") (pin "P$2") (pinfunction "P$2_P$2") (pintype "bidirectional"))
    )
    (net (code "63") (name "Net-(J1001A-S)") (class "Default")
      (node (ref "J1001") (pin "S1") (pinfunction "S_S1") (pintype "passive"))
      (node (ref "L1001") (pin "P$9") (pinfunction "P$2_P$9") (pintype "bidirectional"))
    )
    (net (code "64") (name "Net-(J1001B-S)") (class "Default")
      (node (ref "J1001") (pin "S2") (pinfunction "S_S2") (pintype "passive"))
      (node (ref "L1001") (pin "P$10") (pinfunction "P$2_P$10") (pintype "bidirectional"))
    )
    (net (code "65") (name "Net-(J1001C-S)") (class "Default")
      (node (ref "J1001") (pin "S3") (pinfunction "S_S3") (pintype "passive"))
      (node (ref "L1001") (pin "P$12") (pinfunction "P$2_P$12") (pintype "bidirectional"))
    )
    (net (code "66") (name "Net-(J1001D-S)") (class "Default")
      (node (ref "J1001") (pin "S4") (pinfunction "S_S4") (pintype "passive"))
      (node (ref "L1001") (pin "P$11") (pinfunction "P$2_P$11") (pintype "bidirectional"))
    )
    (net (code "67") (name "Net-(J1001E-S)") (class "Default")
      (node (ref "J1001") (pin "S5") (pinfunction "S_S5") (pintype "passive"))
      (node (ref "L1001") (pin "P$13") (pinfunction "P$2_P$13") (pintype "bidirectional"))
    )
    (net (code "68") (name "Net-(J1001F-S)") (class "Default")
      (node (ref "J1001") (pin "S6") (pinfunction "S_S6") (pintype "passive"))
      (node (ref "L1001") (pin "P$14") (pinfunction "P$2_P$14") (pintype "bidirectional"))
    )
    (net (code "69") (name "Net-(J1001G-S)") (class "Default")
      (node (ref "J1001") (pin "S7") (pinfunction "S_S7") (pintype "passive"))
      (node (ref "L1001") (pin "P$15") (pinfunction "P$2_P$15") (pintype "bidirectional"))
    )
    (net (code "70") (name "Net-(J1001H-S)") (class "Default")
      (node (ref "J1001") (pin "S8") (pinfunction "S_S8") (pintype "passive"))
      (node (ref "L1001") (pin "P$16") (pinfunction "P$2_P$16") (pintype "bidirectional"))
    )
    (net (code "71") (name "Net-(JP201-Pad2)") (class "Default")
      (node (ref "JP201") (pin "2") (pinfunction "2_2") (pintype "passive"))
      (node (ref "JP202") (pin "2") (pinfunction "2_2") (pintype "bidirectional"))
      (node (ref "U$201") (pin "C") (pinfunction "C_C") (pintype "passive"))
    )
    (net (code "72") (name "Net-(JP203-Pad2)") (class "Default")
      (node (ref "JP203") (pin "2") (pinfunction "2_2") (pintype "bidirectional"))
      (node (ref "JP204") (pin "2") (pinfunction "2_2") (pintype "bidirectional"))
      (node (ref "JP205") (pin "2") (pinfunction "2_2") (pintype "bidirectional"))
      (node (ref "L203") (pin "P$2") (pinfunction "P$2_P$2") (pintype "bidirectional"))
      (node (ref "U$204") (pin "C") (pinfunction "C_C") (pintype "passive"))
    )
    (net (code "73") (name "Net-(JP401-Pad1)") (class "Default")
      (node (ref "JP401") (pin "1") (pinfunction "1_1") (pintype "passive"))
      (node (ref "JP402") (pin "1") (pinfunction "1_1") (pintype "passive"))
      (node (ref "L402") (pin "P$2") (pinfunction "P$2_P$2") (pintype "bidirectional"))
      (node (ref "U$401") (pin "C") (pinfunction "C_C") (pintype "passive"))
    )
    (net (code "74") (name "Net-(JP404-Pad1)") (class "Default")
      (node (ref "JP404") (pin "1") (pinfunction "1_1") (pintype "passive"))
      (node (ref "JP405") (pin "1") (pinfunction "1_1") (pintype "passive"))
      (node (ref "L404") (pin "P$2") (pinfunction "P$2_P$2") (pintype "bidirectional"))
      (node (ref "U$402") (pin "C") (pinfunction "C_C") (pintype "passive"))
    )
    (net (code "75") (name "Net-(JP1001-1)") (class "Default")
      (node (ref "JP1001") (pin "P$1") (pinfunction "1_P$1") (pintype "passive"))
      (node (ref "R1001") (pin "P$1") (pinfunction "1_P$1") (pintype "passive"))
    )
    (net (code "76") (name "Net-(JP1002-1)") (class "Default")
      (node (ref "JP1002") (pin "P$1") (pinfunction "1_P$1") (pintype "passive"))
      (node (ref "R1002") (pin "P$1") (pinfunction "1_P$1") (pintype "passive"))
    )
    (net (code "77") (name "Net-(L403B-P$2)") (class "Default")
      (node (ref "JP402") (pin "2") (pinfunction "2_2") (pintype "passive"))
      (node (ref "L403") (pin "P$15") (pinfunction "P$2_P$15") (pintype "bidirectional"))
    )
    (net (code "78") (name "Net-(L403D-P$2)") (class "Default")
      (node (ref "JP401") (pin "2") (pinfunction "2_2") (pintype "passive"))
      (node (ref "L403") (pin "P$13") (pinfunction "P$2_P$13") (pintype "bidirectional"))
    )
    (net (code "79") (name "Net-(L403G-P$2)") (class "Default")
      (node (ref "JP402") (pin "3") (pinfunction "3_3") (pintype "passive"))
      (node (ref "L403") (pin "P$10") (pinfunction "P$2_P$10") (pintype "bidirectional"))
    )
    (net (code "80") (name "Net-(L403H-P$2)") (class "Default")
      (node (ref "JP401") (pin "3") (pinfunction "3_3") (pintype "passive"))
      (node (ref "L403") (pin "P$9") (pinfunction "P$2_P$9") (pintype "bidirectional"))
    )
    (net (code "81") (name "Net-(R101-1)") (class "Default")
      (node (ref "R101") (pin "P$1") (pinfunction "1_P$1") (pintype "passive"))
      (node (ref "U101") (pin "37") (pinfunction "PB2_37") (pintype "bidirectional"))
    )
    (net (code "82") (name "Net-(R201-2)") (class "Default")
      (node (ref "JP202") (pin "1") (pinfunction "1_1") (pintype "bidirectional"))
      (node (ref "R201") (pin "P$2") (pinfunction "2_P$2") (pintype "passive"))
      (node (ref "R202") (pin "P$2") (pinfunction "2_P$2") (pintype "passive"))
      (node (ref "U$202") (pin "C") (pinfunction "C_C") (pintype "passive"))
    )
    (net (code "83") (name "Net-(R407-2)") (class "Default")
      (node (ref "R407") (pin "P$2") (pinfunction "2_P$2") (pintype "passive"))
      (node (ref "SJ402") (pin "1") (pinfunction "1_1") (pintype "passive"))
    )
    (net (code "84") (name "Net-(R408-1)") (class "Default")
      (node (ref "R408") (pin "P$1") (pinfunction "1_P$1") (pintype "passive"))
      (node (ref "SJ401") (pin "2") (pinfunction "2_2") (pintype "passive"))
    )
    (net (code "85") (name "Net-(R408-2)") (class "Default")
      (node (ref "JP404") (pin "3") (pinfunction "3_3") (pintype "passive"))
      (node (ref "R408") (pin "P$2") (pinfunction "2_P$2") (pintype "passive"))
      (node (ref "U401") (pin "6") (pinfunction "CANL_6") (pintype "bidirectional"))
    )
    (net (code "86") (name "Net-(R703-1)") (class "Default")
      (node (ref "R703") (pin "P$1") (pinfunction "1_P$1") (pintype "passive"))
      (node (ref "U$703") (pin "7") (pinfunction "ILIM_7") (pintype "bidirectional"))
    )
    (net (code "87") (name "Net-(R706-2)") (class "Default")
      (node (ref "D701") (pin "C") (pinfunction "C_C") (pintype "passive"))
      (node (ref "R706") (pin "P$2") (pinfunction "2_P$2") (pintype "passive"))
    )
    (net (code "88") (name "Net-(R801-1)") (class "Default")
      (node (ref "JP801") (pin "2") (pinfunction "2_2") (pintype "passive"))
      (node (ref "R801") (pin "P$1") (pinfunction "1_P$1") (pintype "passive"))
    )
    (net (code "89") (name "Net-(R803-1)") (class "Default")
      (node (ref "R803") (pin "P$1") (pinfunction "1_P$1") (pintype "passive"))
      (node (ref "R804") (pin "P$2") (pinfunction "2_P$2") (pintype "passive"))
    )
    (net (code "90") (name "Net-(R803-2)") (class "Default")
      (node (ref "LED801") (pin "C") (pinfunction "C_C") (pintype "passive"))
      (node (ref "R803") (pin "P$2") (pinfunction "2_P$2") (pintype "passive"))
    )
    (net (code "91") (name "Net-(R805-2)") (class "Default")
      (node (ref "LED802") (pin "C") (pinfunction "C_C") (pintype "passive"))
      (node (ref "R805") (pin "P$2") (pinfunction "2_P$2") (pintype "passive"))
    )
    (net (code "92") (name "Net-(R901-1)") (class "Default")
      (node (ref "D901") (pin "C") (pinfunction "C_C") (pintype "passive"))
      (node (ref "R901") (pin "P$1") (pinfunction "1_P$1") (pintype "passive"))
      (node (ref "R902") (pin "P$2") (pinfunction "2_P$2") (pintype "passive"))
    )
    (net (code "93") (name "Net-(U$301-D1I)") (class "Default")
      (node (ref "JP301") (pin "2") (pinfunction "2_2") (pintype "passive"))
      (node (ref "U$301") (pin "1") (pinfunction "D1I_1") (pintype "bidirectional"))
    )
    (net (code "94") (name "Net-(U$301-D2I)") (class "Default")
      (node (ref "JP301") (pin "3") (pinfunction "3_3") (pintype "passive"))
      (node (ref "U$301") (pin "3") (pinfunction "D2I_3") (pintype "bidirectional"))
    )
    (net (code "95") (name "Net-(U$601-L1)") (class "Default")
      (node (ref "L$601") (pin "2") (pinfunction "2_2") (pintype "passive"))
      (node (ref "U$601") (pin "1") (pinfunction "L1_1") (pintype "bidirectional"))
    )
    (net (code "96") (name "Net-(U$601-L2)") (class "Default")
      (node (ref "L$601") (pin "1") (pinfunction "1_1") (pintype "passive"))
      (node (ref "U$601") (pin "14") (pinfunction "L2_14") (pintype "bidirectional"))
    )
    (net (code "97") (name "Net-(U401-CANH)") (class "Default")
      (node (ref "JP404") (pin "2") (pinfunction "2_2") (pintype "passive"))
      (node (ref "SJ401") (pin "1") (pinfunction "1_1") (pintype "passive"))
      (node (ref "U401") (pin "7") (pinfunction "CANH_7") (pintype "bidirectional"))
    )
    (net (code "98") (name "OTG_FS_DM") (class "Default")
      (node (ref "U$301") (pin "6") (pinfunction "D1O_6") (pintype "bidirectional"))
      (node (ref "U101") (pin "70") (pinfunction "PA11_70") (pintype "bidirectional"))
    )
    (net (code "99") (name "OTG_FS_DP") (class "Default")
      (node (ref "U$301") (pin "4") (pinfunction "D2O_4") (pintype "bidirectional"))
      (node (ref "U101") (pin "71") (pinfunction "PA12_71") (pintype "bidirectional"))
    )
    (net (code "100") (name "PPM_INPUT") (class "Default")
      (node (ref "R201") (pin "P$1") (pinfunction "1_P$1") (pintype "passive"))
      (node (ref "R203") (pin "P$1") (pinfunction "1_P$1") (pintype "passive"))
      (node (ref "U$203") (pin "2") (pinfunction "1A_2") (pintype "bidirectional"))
      (node (ref "U101") (pin "23") (pinfunction "PA0_23") (pintype "bidirectional"))
    )
    (net (code "101") (name "SAFETY") (class "Default")
      (node (ref "JP801") (pin "3") (pinfunction "3_3") (pintype "passive"))
      (node (ref "R802") (pin "P$1") (pinfunction "1_P$1") (pintype "passive"))
      (node (ref "U101") (pin "93") (pinfunction "PB7_93") (pintype "bidirectional"))
    )
    (net (code "102") (name "SBUS_OUTPUT_ENABLE") (class "Default")
      (node (ref "R204") (pin "P$2") (pinfunction "2_P$2") (pintype "passive"))
      (node (ref "U$203") (pin "7") (pinfunction "~{2OE}_7") (pintype "input"))
      (node (ref "U101") (pin "91") (pinfunction "PB5_91") (pintype "bidirectional"))
    )
    (net (code "103") (name "SDIO_CK") (class "Default")
      (node (ref "U$302") (pin "6") (pinfunction "CLK_6") (pintype "bidirectional"))
      (node (ref "U101") (pin "80") (pinfunction "PC12_80") (pintype "bidirectional"))
    )
    (net (code "104") (name "SDIO_CMD") (class "Default")
      (node (ref "U$302") (pin "1") (pinfunction "~{CS}_1") (pintype "bidirectional"))
      (node (ref "U101") (pin "83") (pinfunction "PD2_83") (pintype "bidirectional"))
    )
    (net (code "105") (name "SDIO_D0") (class "Default")
      (node (ref "U$302") (pin "5") (pinfunction "DI/IO0_5") (pintype "bidirectional"))
      (node (ref "U101") (pin "65") (pinfunction "PC8_65") (pintype "bidirectional"))
    )
    (net (code "106") (name "SDIO_D1") (class "Default")
      (node (ref "U$302") (pin "2") (pinfunction "DO/IO1_2") (pintype "bidirectional"))
      (node (ref "U101") (pin "66") (pinfunction "PC9_66") (pintype "bidirectional"))
    )
    (net (code "107") (name "SDIO_D2") (class "Default")
      (node (ref "U$302") (pin "3") (pinfunction "~{WP}/IO2_3") (pintype "bidirectional"))
      (node (ref "U101") (pin "78") (pinfunction "PC10_78") (pintype "bidirectional"))
    )
    (net (code "108") (name "SDIO_D3") (class "Default")
      (node (ref "U$302") (pin "7") (pinfunction "~{HOLD}/IO3_7") (pintype "bidirectional"))
      (node (ref "U101") (pin "79") (pinfunction "PC11_79") (pintype "bidirectional"))
    )
    (net (code "109") (name "SERIAL1_CTS") (class "Default")
      (node (ref "JP203") (pin "6") (pinfunction "6_6") (pintype "bidirectional"))
      (node (ref "L201") (pin "P$16") (pinfunction "P$2_P$16") (pintype "bidirectional"))
    )
    (net (code "110") (name "SERIAL1_RTS") (class "Default")
      (node (ref "JP203") (pin "4") (pinfunction "4_4") (pintype "bidirectional"))
      (node (ref "L201") (pin "P$15") (pinfunction "P$2_P$15") (pintype "bidirectional"))
    )
    (net (code "111") (name "SERIAL1_RX") (class "Default")
      (node (ref "JP203") (pin "3") (pinfunction "3_3") (pintype "bidirectional"))
      (node (ref "L201") (pin "P$13") (pinfunction "P$2_P$13") (pintype "bidirectional"))
    )
    (net (code "112") (name "SERIAL1_TX") (class "Default")
      (node (ref "JP203") (pin "1") (pinfunction "1_1") (pintype "bidirectional"))
      (node (ref "L201") (pin "P$14") (pinfunction "P$2_P$14") (pintype "bidirectional"))
    )
    (net (code "113") (name "SERIAL2_CTS") (class "Default")
      (node (ref "JP204") (pin "6") (pinfunction "6_6") (pintype "bidirectional"))
      (node (ref "L201") (pin "P$10") (pinfunction "P$2_P$10") (pintype "bidirectional"))
    )
    (net (code "114") (name "SERIAL2_RTS") (class "Default")
      (node (ref "JP204") (pin "4") (pinfunction "4_4") (pintype "bidirectional"))
      (node (ref "L201") (pin "P$9") (pinfunction "P$2_P$9") (pintype "bidirectional"))
    )
    (net (code "115") (name "SERIAL2_RX") (class "Default")
      (node (ref "JP204") (pin "3") (pinfunction "3_3") (pintype "bidirectional"))
      (node (ref "L201") (pin "P$11") (pinfunction "P$2_P$11") (pintype "bidirectional"))
    )
    (net (code "116") (name "SERIAL2_TX") (class "Default")
      (node (ref "JP204") (pin "1") (pinfunction "1_1") (pintype "bidirectional"))
      (node (ref "L201") (pin "P$12") (pinfunction "P$2_P$12") (pintype "bidirectional"))
    )
    (net (code "117") (name "SERIAL3_RX") (class "Default")
      (node (ref "JP205") (pin "3") (pinfunction "3_3") (pintype "bidirectional"))
      (node (ref "L202") (pin "P$9") (pinfunction "P$2_P$9") (pintype "bidirectional"))
    )
    (net (code "118") (name "SERIAL3_TX") (class "Default")
      (node (ref "JP205") (pin "1") (pinfunction "1_1") (pintype "bidirectional"))
      (node (ref "L202") (pin "P$11") (pinfunction "P$2_P$11") (pintype "bidirectional"))
    )
    (net (code "119") (name "SPEKTRUM_RX") (class "Default")
      (node (ref "R202") (pin "P$1") (pinfunction "1_P$1") (pintype "passive"))
      (node (ref "U101") (pin "69") (pinfunction "PA10_69") (pintype "bidirectional"))
    )
    (net (code "120") (name "SPI_EXT_MISO") (class "Default")
      (node (ref "J401") (pin "3") (pinfunction "3_3") (pintype "passive"))
      (node (ref "U101") (pin "4") (pinfunction "PE5_4") (pintype "bidirectional"))
    )
    (net (code "121") (name "SPI_EXT_MOSI") (class "Default")
      (node (ref "J401") (pin "6") (pinfunction "6_6") (pintype "passive"))
      (node (ref "U101") (pin "5") (pinfunction "PE6_5") (pintype "bidirectional"))
    )
    (net (code "122") (name "SPI_EXT_SCK") (class "Default")
      (node (ref "J401") (pin "2") (pinfunction "2_2") (pintype "passive"))
      (node (ref "U101") (pin "1") (pinfunction "PE2_1") (pintype "bidirectional"))
    )
    (net (code "123") (name "SPI_INT_MISO") (class "Default")
      (node (ref "U$501") (pin "7") (pinfunction "SA0/MISO_7") (pintype "bidirectional"))
      (node (ref "U101") (pin "31") (pinfunction "PA6_31") (pintype "bidirectional"))
    )
    (net (code "124") (name "SPI_INT_MOSI") (class "Default")
      (node (ref "U$501") (pin "6") (pinfunction "SDA/MOSI_6") (pintype "bidirectional"))
      (node (ref "U101") (pin "32") (pinfunction "PA7_32") (pintype "bidirectional"))
    )
    (net (code "125") (name "SPI_INT_SCK") (class "Default")
      (node (ref "U$501") (pin "4") (pinfunction "SCL/CLK_4") (pintype "bidirectional"))
      (node (ref "U101") (pin "30") (pinfunction "PA5_30") (pintype "bidirectional"))
    )
    (net (code "126") (name "VBAT") (class "Default")
      (node (ref "R706") (pin "P$1") (pinfunction "1_P$1") (pintype "passive"))
      (node (ref "U$704") (pin "1") (pinfunction "POS_1") (pintype "bidirectional"))
      (node (ref "U101") (pin "6") (pinfunction "VBAT_6") (pintype "power_in"))
    )
    (net (code "127") (name "VBUS") (class "Default")
      (node (ref "D904") (pin "ANODE") (pinfunction "A_ANODE") (pintype "passive"))
      (node (ref "JP301") (pin "1") (pinfunction "1_1") (pintype "passive"))
      (node (ref "U$301") (pin "5") (pinfunction "VBUS_5") (pintype "bidirectional"))
      (node (ref "U101") (pin "68") (pinfunction "PA9_68") (pintype "bidirectional"))
    )
    (net (code "128") (name "VDD_3V3_SENSORS") (class "Default")
      (node (ref "C501") (pin "P$1") (pinfunction "1_P$1") (pintype "passive"))
      (node (ref "C502") (pin "P$1") (pinfunction "1_P$1") (pintype "passive"))
      (node (ref "C707") (pin "P$1") (pinfunction "1_P$1") (pintype "passive"))
      (node (ref "U$501") (pin "1") (pinfunction "VDD_IO_1") (pintype "power_in"))
      (node (ref "U$501") (pin "14") (pinfunction "VDD_14") (pintype "power_in"))
      (node (ref "U$501") (pin "15") (pinfunction "RSV2_15") (pintype "input"))
      (node (ref "U$702") (pin "8") (pinfunction "VOUT1_8") (pintype "bidirectional"))
    )
    (net (code "129") (name "VDD_3V3_SENSORS_EN") (class "Default")
      (node (ref "R702") (pin "P$2") (pinfunction "2_P$2") (pintype "passive"))
      (node (ref "U$702") (pin "5") (pinfunction "EN1_5") (pintype "bidirectional"))
      (node (ref "U101") (pin "2") (pinfunction "PE3_2") (pintype "bidirectional"))
    )
    (net (code "130") (name "VDD_3V3_SPEKTRUM") (class "Default")
      (node (ref "C708") (pin "P$1") (pinfunction "1_P$1") (pintype "passive"))
      (node (ref "JP201") (pin "1") (pinfunction "1_1") (pintype "passive"))
      (node (ref "U$701") (pin "8") (pinfunction "VOUT1_8") (pintype "bidirectional"))
    )
    (net (code "131") (name "VDD_3V3_SPEKTRUM_EN") (class "Default")
      (node (ref "R701") (pin "P$2") (pinfunction "2_P$2") (pintype "passive"))
      (node (ref "U$701") (pin "5") (pinfunction "EN1_5") (pintype "bidirectional"))
      (node (ref "U101") (pin "17") (pinfunction "PC2_17") (pintype "bidirectional"))
    )
    (net (code "132") (name "VDD_5V") (class "Default")
      (node (ref "C604") (pin "1") (pinfunction "1_1") (pintype "passive"))
      (node (ref "C605") (pin "1") (pinfunction "1_1") (pintype "passive"))
      (node (ref "C606") (pin "1") (pinfunction "1_1") (pintype "passive"))
      (node (ref "C701") (pin "P$1") (pinfunction "1_P$1") (pintype "passive"))
      (node (ref "C702") (pin "P$1") (pinfunction "1_P$1") (pintype "passive"))
      (node (ref "LED801") (pin "A") (pinfunction "A_A") (pintype "passive"))
      (node (ref "LED802") (pin "A") (pinfunction "A_A") (pintype "passive"))
      (node (ref "R707") (pin "P$2") (pinfunction "2_P$2") (pintype "passive"))
      (node (ref "U$601") (pin "13") (pinfunction "VOUT_13") (pintype "power_in"))
      (node (ref "U$701") (pin "1") (pinfunction "VIN_1") (pintype "bidirectional"))
      (node (ref "U$701") (pin "4") (pinfunction "EN2_4") (pintype "bidirectional"))
      (node (ref "U$702") (pin "1") (pinfunction "VIN_1") (pintype "bidirectional"))
      (node (ref "U$703") (pin "1") (pinfunction "IN_1") (pintype "bidirectional"))
    )
    (net (code "133") (name "VDD_5V_PERIPH") (class "Default")
      (node (ref "JP201") (pin "3") (pinfunction "3_3") (pintype "passive"))
      (node (ref "L203") (pin "P$1") (pinfunction "P$1_P$1") (pintype "bidirectional"))
      (node (ref "L401") (pin "P$1") (pinfunction "P$1_P$1") (pintype "bidirectional"))
      (node (ref "L402") (pin "P$1") (pinfunction "P$1_P$1") (pintype "bidirectional"))
      (node (ref "L404") (pin "P$1") (pinfunction "P$1_P$1") (pintype "bidirectional"))
      (node (ref "U$703") (pin "8") (pinfunction "OUT_8") (pintype "bidirectional"))
    )
    (net (code "134") (name "VDD_5V_SENS") (class "Default")
      (node (ref "R707") (pin "P$1") (pinfunction "1_P$1") (pintype "passive"))
      (node (ref "R708") (pin "P$1") (pinfunction "1_P$1") (pintype "passive"))
      (node (ref "U101") (pin "29") (pinfunction "PA4_29") (pintype "bidirectional"))
    )
    (net (code "135") (name "VDD_IN") (class "Default")
      (node (ref "C601") (pin "1") (pinfunction "1_1") (pintype "passive"))
      (node (ref "C602") (pin "P$1") (pinfunction "1_P$1") (pintype "passive"))
      (node (ref "D902") (pin "C") (pinfunction "C_C") (pintype "passive"))
      (node (ref "D903") (pin "C") (pinfunction "C_C") (pintype "passive"))
      (node (ref "D904") (pin "CATHODE") (pinfunction "C_CATHODE") (pintype "passive"))
      (node (ref "U$601") (pin "2") (pinfunction "VIN_2") (pintype "power_in"))
      (node (ref "U$601") (pin "3") (pinfunction "EN_3") (pintype "input"))
    )
    (net (code "136") (name "VDD_SERVO_SENSE") (class "Default")
      (node (ref "R902") (pin "P$1") (pinfunction "1_P$1") (pintype "passive"))
      (node (ref "R903") (pin "P$2") (pinfunction "2_P$2") (pintype "passive"))
      (node (ref "U101") (pin "16") (pinfunction "PC1_16") (pintype "bidirectional"))
    )
    (net (code "137") (name "V_EXT") (class "Default")
      (node (ref "D903") (pin "A") (pinfunction "A_A") (pintype "passive"))
      (node (ref "JP901") (pin "1") (pinfunction "1_1") (pintype "passive"))
      (node (ref "R901") (pin "P$2") (pinfunction "2_P$2") (pintype "passive"))
    )
    (net (code "138") (name "V_SERVO") (class "Default")
      (node (ref "D902") (pin "A") (pinfunction "A_A") (pintype "passive"))
      (node (ref "J1001") (pin "PWR_S1") (pinfunction "S_PWR_S1") (pintype "passive"))
      (node (ref "J1001") (pin "PWR_S2") (pinfunction "S_PWR_S2") (pintype "passive"))
      (node (ref "J1001") (pin "PWR_S3") (pinfunction "S_PWR_S3") (pintype "passive"))
      (node (ref "J1001") (pin "PWR_S4") (pinfunction "S_PWR_S4") (pintype "passive"))
      (node (ref "J1001") (pin "PWR_S5") (pinfunction "S_PWR_S5") (pintype "passive"))
      (node (ref "J1001") (pin "PWR_S6") (pinfunction "S_PWR_S6") (pintype "passive"))
      (node (ref "J1001") (pin "PWR_S7") (pinfunction "S_PWR_S7") (pintype "passive"))
      (node (ref "J1001") (pin "PWR_S8") (pinfunction "S_PWR_S8") (pintype "passive"))
    )
    (net (code "139") (name "unconnected-(J401-Pad1)") (class "Default")
      (node (ref "J401") (pin "1") (pinfunction "1_1") (pintype "passive"))
    )
    (net (code "140") (name "unconnected-(JP205-Pad4)") (class "Default")
      (node (ref "JP205") (pin "4") (pinfunction "4_4") (pintype "bidirectional"))
    )
    (net (code "141") (name "unconnected-(JP205-Pad6)") (class "Default")
      (node (ref "JP205") (pin "6") (pinfunction "6_6") (pintype "bidirectional"))
    )
    (net (code "142") (name "unconnected-(JX301F-S-Pad8)") (class "Default")
      (node (ref "JX301") (pin "8") (pinfunction "S_8") (pintype "passive"))
    )
    (net (code "143") (name "unconnected-(L202-PadP$1)") (class "Default")
      (node (ref "L202") (pin "P$1") (pinfunction "P$1_P$1") (pintype "bidirectional"))
    )
    (net (code "144") (name "unconnected-(L202A-P$2-PadP$16)") (class "Default")
      (node (ref "L202") (pin "P$16") (pinfunction "P$2_P$16") (pintype "bidirectional"))
    )
    (net (code "145") (name "unconnected-(L202B-P$1-PadP$2)") (class "Default")
      (node (ref "L202") (pin "P$2") (pinfunction "P$1_P$2") (pintype "bidirectional"))
    )
    (net (code "146") (name "unconnected-(L202B-P$2-PadP$15)") (class "Default")
      (node (ref "L202") (pin "P$15") (pinfunction "P$2_P$15") (pintype "bidirectional"))
    )
    (net (code "147") (name "unconnected-(L202C-P$1-PadP$3)") (class "Default")
      (node (ref "L202") (pin "P$3") (pinfunction "P$1_P$3") (pintype "bidirectional"))
    )
    (net (code "148") (name "unconnected-(L202C-P$2-PadP$14)") (class "Default")
      (node (ref "L202") (pin "P$14") (pinfunction "P$2_P$14") (pintype "bidirectional"))
    )
    (net (code "149") (name "unconnected-(L202D-P$1-PadP$4)") (class "Default")
      (node (ref "L202") (pin "P$4") (pinfunction "P$1_P$4") (pintype "bidirectional"))
    )
    (net (code "150") (name "unconnected-(L202D-P$2-PadP$13)") (class "Default")
      (node (ref "L202") (pin "P$13") (pinfunction "P$2_P$13") (pintype "bidirectional"))
    )
    (net (code "151") (name "unconnected-(L202E-P$1-PadP$5)") (class "Default")
      (node (ref "L202") (pin "P$5") (pinfunction "P$1_P$5") (pintype "bidirectional"))
    )
    (net (code "152") (name "unconnected-(L202E-P$2-PadP$12)") (class "Default")
      (node (ref "L202") (pin "P$12") (pinfunction "P$2_P$12") (pintype "bidirectional"))
    )
    (net (code "153") (name "unconnected-(L202G-P$1-PadP$7)") (class "Default")
      (node (ref "L202") (pin "P$7") (pinfunction "P$1_P$7") (pintype "bidirectional"))
    )
    (net (code "154") (name "unconnected-(L202G-P$2-PadP$10)") (class "Default")
      (node (ref "L202") (pin "P$10") (pinfunction "P$2_P$10") (pintype "bidirectional"))
    )
    (net (code "155") (name "unconnected-(U$501-MST_SCL-Pad2)") (class "Default")
      (node (ref "U$501") (pin "2") (pinfunction "MST_SCL_2") (pintype "bidirectional"))
    )
    (net (code "156") (name "unconnected-(U$501-MST_SDA-Pad3)") (class "Default")
      (node (ref "U$501") (pin "3") (pinfunction "MST_SDA_3") (pintype "bidirectional"))
    )
    (net (code "157") (name "unconnected-(U$501-RSV3-Pad16)") (class "Default")
      (node (ref "U$501") (pin "16") (pinfunction "RSV3_16") (pintype "no_connect"))
    )
    (net (code "158") (name "unconnected-(U$601-FB-Pad12)") (class "Default")
      (node (ref "U$601") (pin "12") (pinfunction "FB_12") (pintype "input"))
    )
    (net (code "159") (name "unconnected-(U$601-PG-Pad5)") (class "Default")
      (node (ref "U$601") (pin "5") (pinfunction "PG_5") (pintype "output"))
    )
    (net (code "160") (name "unconnected-(U$702-VOUT2-Pad7)") (class "Default")
      (node (ref "U$702") (pin "7") (pinfunction "VOUT2_7") (pintype "bidirectional"))
    )
    (net (code "161") (name "unconnected-(U101I-PC0-Pad15)") (class "Default")
      (node (ref "U101") (pin "15") (pinfunction "PC0_15") (pintype "bidirectional"))
    )
    (net (code "162") (name "unconnected-(U101I-PC5-Pad34)") (class "Default")
      (node (ref "U101") (pin "34") (pinfunction "PC5_34") (pintype "bidirectional"))
    )
    (net (code "163") (name "unconnected-(U101I-PC6-Pad63)") (class "Default")
      (node (ref "U101") (pin "63") (pinfunction "PC6_63") (pintype "bidirectional"))
    )
    (net (code "164") (name "unconnected-(U101I-PC7-Pad64)") (class "Default")
      (node (ref "U101") (pin "64") (pinfunction "PC7_64") (pintype "bidirectional"))
    )
    (net (code "165") (name "unconnected-(U101L-PE10-Pad41)") (class "Default")
      (node (ref "U101") (pin "41") (pinfunction "PE10_41") (pintype "bidirectional"))
    )
    (net (code "166") (name "~{BARO_CS}") (class "Default")
      (node (ref "U101") (pin "88") (pinfunction "PD7_88") (pintype "bidirectional"))
    )
    (net (code "167") (name "~{FMU-LED_AMBER}") (class "Default")
      (node (ref "R804") (pin "P$1") (pinfunction "1_P$1") (pintype "passive"))
      (node (ref "U101") (pin "43") (pinfunction "PE12_43") (pintype "bidirectional"))
    )
    (net (code "168") (name "~{FRAM_CS}") (class "Default")
      (node (ref "U101") (pin "57") (pinfunction "PD10_57") (pintype "bidirectional"))
    )
    (net (code "169") (name "~{GYRO_CS}") (class "Default")
      (node (ref "U$501") (pin "8") (pinfunction "CS_8") (pintype "bidirectional"))
      (node (ref "U101") (pin "7") (pinfunction "PC13_7") (pintype "bidirectional"))
    )
    (net (code "170") (name "~{SPI_EXT_NSS}") (class "Default")
      (node (ref "J401") (pin "4") (pinfunction "4_4") (pintype "passive"))
      (node (ref "U101") (pin "3") (pinfunction "PE4_3") (pintype "bidirectional"))
    )
    (net (code "171") (name "~{VDD_5V_PERIPH_EN}") (class "Default")
      (node (ref "R704") (pin "P$2") (pinfunction "2_P$2") (pintype "passive"))
      (node (ref "U$703") (pin "5") (pinfunction "~{CE}_5") (pintype "bidirectional"))
      (node (ref "U101") (pin "67") (pinfunction "PA8_67") (pintype "bidirectional"))
    )
    (net (code "172") (name "~{VDD_5V_PERIPH_OC}") (class "Default")
      (node (ref "R705") (pin "P$2") (pinfunction "2_P$2") (pintype "passive"))
      (node (ref "U$703") (pin "4") (pinfunction "~{FAULT}_4") (pintype "bidirectional"))
      (node (ref "U101") (pin "46") (pinfunction "PE15_46") (pintype "bidirectional"))
    )
  )
)
